# dental-uint-doctors_table_v1_0.net
KiCad netlist of a schematic drawn in Altium Designer
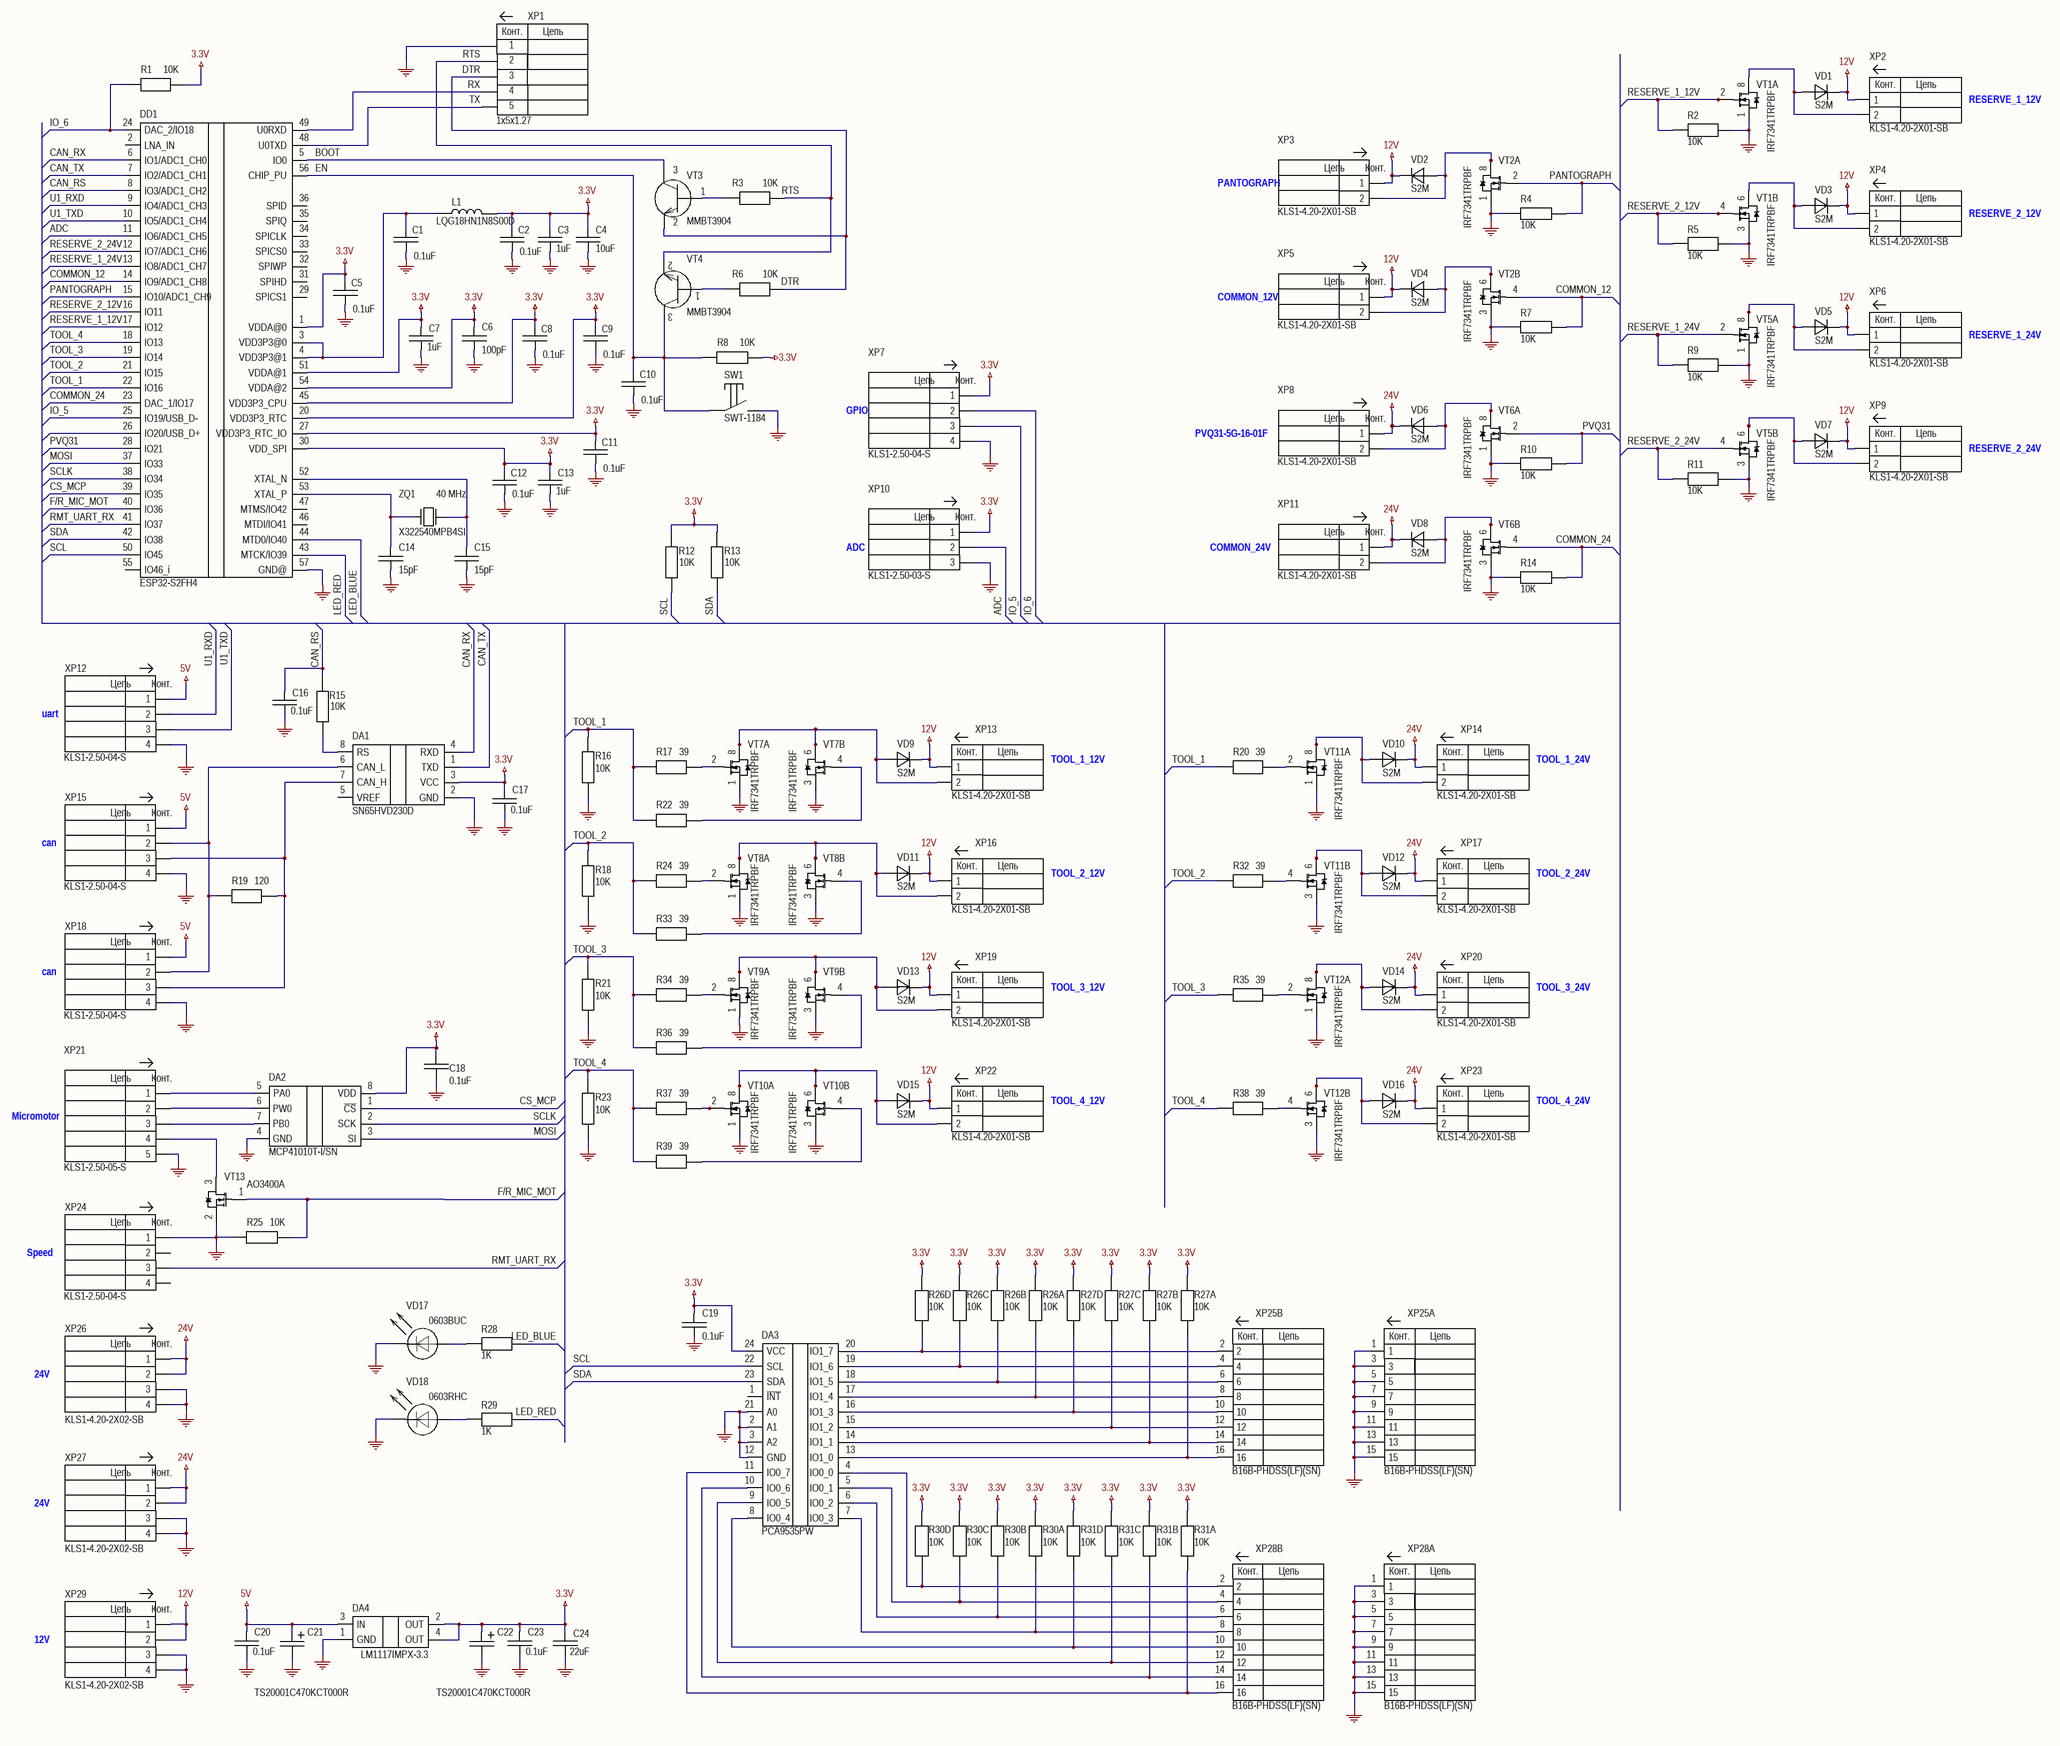
[diagram p0: dental-uint-doctors_table v1_0.SchDoc]

(export (version "E")
  (design (tool "Eeschema 10.0.6"))
  (components
    (comp (ref "C1")
      (value "0.1uF")
      (footprint "CC_0603")
      (description "Cap Ceramic, 0603, 0.1u, 10%, 16V, X7R (Yageo)")
      (fields (field (name "Comment") "CC0603KRX7R5BB104"))
      (libsource (lib "my_discrete_new") (part "C"))
    )
    (comp (ref "C2")
      (value "0.1uF")
      (footprint "CC_0603")
      (description "Cap Ceramic, 0603, 0.1u, 10%, 16V, X7R (Yageo)")
      (fields (field (name "Comment") "CC0603KRX7R5BB104"))
      (libsource (lib "my_discrete_new") (part "C"))
    )
    (comp (ref "C3")
      (value "1uF")
      (footprint "CC_0603")
      (description "Cap Ceramic, 0603, 1u, 10%, 50V, X5R (Sumsung)")
      (fields (field (name "Comment") "CL10A105KB8NNNC"))
      (libsource (lib "my_discrete_new") (part "C"))
    )
    (comp (ref "C4")
      (value "10uF")
      (footprint "CC_0603")
      (description "Cap Ceramic, 0603, 10u, 10%, 16V, X5R (Sumsung)")
      (fields (field (name "Comment") "CL10A106KP8NNNC"))
      (libsource (lib "my_discrete_new") (part "C"))
    )
    (comp (ref "C5")
      (value "0.1uF")
      (footprint "CC_0603")
      (description "Cap Ceramic, 0603, 0.1u, 10%, 16V, X7R (Yageo)")
      (fields (field (name "Comment") "CC0603KRX7R5BB104"))
      (libsource (lib "my_discrete_new") (part "C"))
    )
    (comp (ref "C6")
      (value "100pF")
      (footprint "CC_0603")
      (description "Cap Ceramic, 0603, 100p, 1%, 50V, NP0 (Yageo)")
      (fields (field (name "Comment") "CC0603FRNPO9BN101"))
      (libsource (lib "my_discrete_new") (part "C"))
    )
    (comp (ref "C7")
      (value "1uF")
      (footprint "CC_0603")
      (description "Cap Ceramic, 0603, 1u, 10%, 50V, X5R (Sumsung)")
      (fields (field (name "Comment") "CL10A105KB8NNNC"))
      (libsource (lib "my_discrete_new") (part "C"))
    )
    (comp (ref "C8")
      (value "0.1uF")
      (footprint "CC_0603")
      (description "Cap Ceramic, 0603, 0.1u, 10%, 16V, X7R (Yageo)")
      (fields (field (name "Comment") "CC0603KRX7R5BB104"))
      (libsource (lib "my_discrete_new") (part "C"))
    )
    (comp (ref "C9")
      (value "0.1uF")
      (footprint "CC_0603")
      (description "Cap Ceramic, 0603, 0.1u, 10%, 16V, X7R (Yageo)")
      (fields (field (name "Comment") "CC0603KRX7R5BB104"))
      (libsource (lib "my_discrete_new") (part "C"))
    )
    (comp (ref "C10")
      (value "0.1uF")
      (footprint "CC_0603")
      (description "Cap Ceramic, 0603, 0.1u, 10%, 16V, X7R (Yageo)")
      (fields (field (name "Comment") "CC0603KRX7R5BB104"))
      (libsource (lib "my_discrete_new") (part "C"))
    )
    (comp (ref "C11")
      (value "0.1uF")
      (footprint "CC_0603")
      (description "Cap Ceramic, 0603, 0.1u, 10%, 16V, X7R (Yageo)")
      (fields (field (name "Comment") "CC0603KRX7R5BB104"))
      (libsource (lib "my_discrete_new") (part "C"))
    )
    (comp (ref "C12")
      (value "0.1uF")
      (footprint "CC_0603")
      (description "Cap Ceramic, 0603, 0.1u, 10%, 16V, X7R (Yageo)")
      (fields (field (name "Comment") "CC0603KRX7R5BB104"))
      (libsource (lib "my_discrete_new") (part "C"))
    )
    (comp (ref "C13")
      (value "1uF")
      (footprint "CC_0603")
      (description "Cap Ceramic, 0603, 1u, 10%, 50V, X5R (Sumsung)")
      (fields (field (name "Comment") "CL10A105KB8NNNC"))
      (libsource (lib "my_discrete_new") (part "C"))
    )
    (comp (ref "C14")
      (value "15pF")
      (footprint "CC_0603")
      (description "Cap Ceramic, 0603, 15pF, 50V, NP0 (Yageo)")
      (fields (field (name "Comment") "CC0603GPNPO9BN150"))
      (libsource (lib "my_discrete_new") (part "C"))
    )
    (comp (ref "C15")
      (value "15pF")
      (footprint "CC_0603")
      (description "Cap Ceramic, 0603, 15pF, 50V, NP0 (Yageo)")
      (fields (field (name "Comment") "CC0603GPNPO9BN150"))
      (libsource (lib "my_discrete_new") (part "C"))
    )
    (comp (ref "C16")
      (value "0.1uF")
      (footprint "CC_0603")
      (description "Cap Ceramic, 0603, 0.1u, 10%, 16V, X7R (Yageo)")
      (fields (field (name "Comment") "CC0603KRX7R5BB104"))
      (libsource (lib "my_discrete_new") (part "C"))
    )
    (comp (ref "C17")
      (value "0.1uF")
      (footprint "CC_0603")
      (description "Cap Ceramic, 0603, 0.1u, 10%, 16V, X7R (Yageo)")
      (fields (field (name "Comment") "CC0603KRX7R5BB104"))
      (libsource (lib "my_discrete_new") (part "C"))
    )
    (comp (ref "C18")
      (value "0.1uF")
      (footprint "CC_0603")
      (description "Cap Ceramic, 0603, 0.1u, 10%, 16V, X7R (Yageo)")
      (fields (field (name "Comment") "CC0603KRX7R5BB104"))
      (libsource (lib "my_discrete_new") (part "C"))
    )
    (comp (ref "C19")
      (value "0.1uF")
      (footprint "CC_0603")
      (description "Cap Ceramic, 0603, 0.1u, 10%, 16V, X7R (Yageo)")
      (fields (field (name "Comment") "CC0603KRX7R5BB104"))
      (libsource (lib "my_discrete_new") (part "C"))
    )
    (comp (ref "C20")
      (value "0.1uF")
      (footprint "CC_0603")
      (description "Cap Ceramic, 0603, 0.1u, 10%, 16V, X7R (Yageo)")
      (fields (field (name "Comment") "CC0603KRX7R5BB104"))
      (libsource (lib "my_discrete_new") (part "C"))
    )
    (comp (ref "C21")
      (value "TS20001C470KCT000R")
      (footprint "CC_TANT_C")
      (description "47uF, 16v, C, 10%, @SUNTAN,")
      (libsource (lib "my_discrete_new") (part "C_polar"))
    )
    (comp (ref "C22")
      (value "TS20001C470KCT000R")
      (footprint "CC_TANT_C")
      (description "47uF, 16v, C, 10%, @SUNTAN,")
      (libsource (lib "my_discrete_new") (part "C_polar"))
    )
    (comp (ref "C23")
      (value "0.1uF")
      (footprint "CC_0603")
      (description "Cap Ceramic, 0603, 0.1u, 10%, 16V, X7R (Yageo)")
      (fields (field (name "Comment") "CC0603KRX7R5BB104"))
      (libsource (lib "my_discrete_new") (part "C"))
    )
    (comp (ref "C24")
      (value "22uF")
      (footprint "CC_0805")
      (description "Cap Ceramic, 0805, 22u, 20%, 6.3V, X5R, -55 +85C (Murata)")
      (fields (field (name "Comment") "GRM21BR60J226ME39L"))
      (libsource (lib "my_discrete_new") (part "C"))
    )
    (comp (ref "DA1")
      (value "SN65HVD230D")
      (footprint "SOIC-8")
      (description "3.3-V CAN TRANSCEIVERS, @TI")
      (libsource (lib "my_microschems_new") (part "SN65HVD230D"))
    )
    (comp (ref "DA2")
      (value "MCP41010T-I/SN")
      (footprint "SOIC-8")
      (description "Single/Dual Digital Potentiometer, 10k, @MICROCHIP")
      (libsource (lib "my_microschems_new") (part "MCP41010T-I/SN"))
    )
    (comp (ref "DA3")
      (value "PCA9535PW")
      (footprint "TSSOP-24")
      (description "I2C I/O EXPANDER")
      (libsource (lib "my_microschems_new") (part "PCA9535PW"))
    )
    (comp (ref "DA4")
      (value "LM1117IMPX-3.3")
      (footprint "SOT-223")
      (description "LDO, 3.3v, 0.8A, SOT-223, Texas Instruments")
      (libsource (lib "my_microschems_new") (part "LM1117IMPX-3.3"))
    )
    (comp (ref "DD1")
      (value "ESP32-S2FH4")
      (footprint "QFN40P700X700X90-57T400N")
      (description "SMD WI-FI IC, ESP32-S2FH4, SINGAL-C")
      (fields (field (name "MF") "Espressif Systems") (field (name "MP") "ESP32-S2"))
      (libsource (lib "my_microschems_new") (part "ESP32-S2"))
    )
    (comp (ref "L1")
      (value "LQG18HN1N8S00D")
      (footprint "IC_0603")
      (description "1.1A, 1.8nH,100mΩ, 0603, Inductors (SMD), @MURATA")
      (libsource (lib "my_discrete_new") (part "L"))
    )
    (comp (ref "R1")
      (value "10K")
      (footprint "RC_0603")
      (description "Res, 0603, 10K, 1%, 0.25W (ф. Yageo)")
      (fields (field (name "POWER") "0.25W") (field (name "Comment") "AC0603FR-0710KL"))
      (libsource (lib "my_discrete_new") (part "R"))
    )
    (comp (ref "R2")
      (value "10K")
      (footprint "RC_0603")
      (description "Res, 0603, 10K, 1%, 0.25W (ф. Yageo)")
      (fields (field (name "POWER") "0.25W") (field (name "Comment") "AC0603FR-0710KL"))
      (libsource (lib "my_discrete_new") (part "R"))
    )
    (comp (ref "R3")
      (value "10K")
      (footprint "RC_0603")
      (description "Res, 0603, 10K, 1%, 0.25W (ф. Yageo)")
      (fields (field (name "POWER") "0.25W") (field (name "Comment") "AC0603FR-0710KL"))
      (libsource (lib "my_discrete_new") (part "R"))
    )
    (comp (ref "R4")
      (value "10K")
      (footprint "RC_0603")
      (description "Res, 0603, 10K, 1%, 0.25W (ф. Yageo)")
      (fields (field (name "POWER") "0.25W") (field (name "Comment") "AC0603FR-0710KL"))
      (libsource (lib "my_discrete_new") (part "R"))
    )
    (comp (ref "R5")
      (value "10K")
      (footprint "RC_0603")
      (description "Res, 0603, 10K, 1%, 0.25W (ф. Yageo)")
      (fields (field (name "POWER") "0.25W") (field (name "Comment") "AC0603FR-0710KL"))
      (libsource (lib "my_discrete_new") (part "R"))
    )
    (comp (ref "R6")
      (value "10K")
      (footprint "RC_0603")
      (description "Res, 0603, 10K, 1%, 0.25W (ф. Yageo)")
      (fields (field (name "POWER") "0.25W") (field (name "Comment") "AC0603FR-0710KL"))
      (libsource (lib "my_discrete_new") (part "R"))
    )
    (comp (ref "R7")
      (value "10K")
      (footprint "RC_0603")
      (description "Res, 0603, 10K, 1%, 0.25W (ф. Yageo)")
      (fields (field (name "POWER") "0.25W") (field (name "Comment") "AC0603FR-0710KL"))
      (libsource (lib "my_discrete_new") (part "R"))
    )
    (comp (ref "R8")
      (value "10K")
      (footprint "RC_0603")
      (description "Res, 0603, 10K, 1%, 0.25W (ф. Yageo)")
      (fields (field (name "POWER") "0.25W") (field (name "Comment") "AC0603FR-0710KL"))
      (libsource (lib "my_discrete_new") (part "R"))
    )
    (comp (ref "R9")
      (value "10K")
      (footprint "RC_0603")
      (description "Res, 0603, 10K, 1%, 0.25W (ф. Yageo)")
      (fields (field (name "POWER") "0.25W") (field (name "Comment") "AC0603FR-0710KL"))
      (libsource (lib "my_discrete_new") (part "R"))
    )
    (comp (ref "R10")
      (value "10K")
      (footprint "RC_0603")
      (description "Res, 0603, 10K, 1%, 0.25W (ф. Yageo)")
      (fields (field (name "POWER") "0.25W") (field (name "Comment") "AC0603FR-0710KL"))
      (libsource (lib "my_discrete_new") (part "R"))
    )
    (comp (ref "R11")
      (value "10K")
      (footprint "RC_0603")
      (description "Res, 0603, 10K, 1%, 0.25W (ф. Yageo)")
      (fields (field (name "POWER") "0.25W") (field (name "Comment") "AC0603FR-0710KL"))
      (libsource (lib "my_discrete_new") (part "R"))
    )
    (comp (ref "R12")
      (value "10K")
      (footprint "RC_0603")
      (description "Res, 0603, 10K, 1%, 0.25W (ф. Yageo)")
      (fields (field (name "POWER") "0.25W") (field (name "Comment") "AC0603FR-0710KL"))
      (libsource (lib "my_discrete_new") (part "R"))
    )
    (comp (ref "R13")
      (value "10K")
      (footprint "RC_0603")
      (description "Res, 0603, 10K, 1%, 0.25W (ф. Yageo)")
      (fields (field (name "POWER") "0.25W") (field (name "Comment") "AC0603FR-0710KL"))
      (libsource (lib "my_discrete_new") (part "R"))
    )
    (comp (ref "R14")
      (value "10K")
      (footprint "RC_0603")
      (description "Res, 0603, 10K, 1%, 0.25W (ф. Yageo)")
      (fields (field (name "POWER") "0.25W") (field (name "Comment") "AC0603FR-0710KL"))
      (libsource (lib "my_discrete_new") (part "R"))
    )
    (comp (ref "R15")
      (value "10K")
      (footprint "RC_0603")
      (description "Res, 0603, 10K, 1%, 0.25W (ф. Yageo)")
      (fields (field (name "POWER") "0.25W") (field (name "Comment") "AC0603FR-0710KL"))
      (libsource (lib "my_discrete_new") (part "R"))
    )
    (comp (ref "R16")
      (value "10K")
      (footprint "RC_0603")
      (description "Res, 0603, 10K, 1%, 0.25W (ф. Yageo)")
      (fields (field (name "POWER") "0.25W") (field (name "Comment") "AC0603FR-0710KL"))
      (libsource (lib "my_discrete_new") (part "R"))
    )
    (comp (ref "R17")
      (value "39")
      (footprint "RC_0603")
      (description "Res, 0603, 39, 1%, 0.25W (ф. Yageo)")
      (fields (field (name "POWER") "0.25W") (field (name "Comment") "RC0603FR-0739RL"))
      (libsource (lib "my_discrete_new") (part "R"))
    )
    (comp (ref "R18")
      (value "10K")
      (footprint "RC_0603")
      (description "Res, 0603, 10K, 1%, 0.25W (ф. Yageo)")
      (fields (field (name "POWER") "0.25W") (field (name "Comment") "AC0603FR-0710KL"))
      (libsource (lib "my_discrete_new") (part "R"))
    )
    (comp (ref "R19")
      (value "120")
      (footprint "RC_0603")
      (description "Res, 0603, 120, 1%, 0.25W (ф. Yageo)")
      (fields (field (name "POWER") "0.25W") (field (name "Comment") "RC0603FR-07120RL"))
      (libsource (lib "my_discrete_new") (part "R"))
    )
    (comp (ref "R20")
      (value "39")
      (footprint "RC_0603")
      (description "Res, 0603, 39, 1%, 0.25W (ф. Yageo)")
      (fields (field (name "POWER") "0.25W") (field (name "Comment") "RC0603FR-0739RL"))
      (libsource (lib "my_discrete_new") (part "R"))
    )
    (comp (ref "R21")
      (value "10K")
      (footprint "RC_0603")
      (description "Res, 0603, 10K, 1%, 0.25W (ф. Yageo)")
      (fields (field (name "POWER") "0.25W") (field (name "Comment") "AC0603FR-0710KL"))
      (libsource (lib "my_discrete_new") (part "R"))
    )
    (comp (ref "R22")
      (value "39")
      (footprint "RC_0603")
      (description "Res, 0603, 39, 1%, 0.25W (ф. Yageo)")
      (fields (field (name "POWER") "0.25W") (field (name "Comment") "RC0603FR-0739RL"))
      (libsource (lib "my_discrete_new") (part "R"))
    )
    (comp (ref "R23")
      (value "10K")
      (footprint "RC_0603")
      (description "Res, 0603, 10K, 1%, 0.25W (ф. Yageo)")
      (fields (field (name "POWER") "0.25W") (field (name "Comment") "AC0603FR-0710KL"))
      (libsource (lib "my_discrete_new") (part "R"))
    )
    (comp (ref "R24")
      (value "39")
      (footprint "RC_0603")
      (description "Res, 0603, 39, 1%, 0.25W (ф. Yageo)")
      (fields (field (name "POWER") "0.25W") (field (name "Comment") "RC0603FR-0739RL"))
      (libsource (lib "my_discrete_new") (part "R"))
    )
    (comp (ref "R25")
      (value "10K")
      (footprint "RC_0603")
      (description "Res, 0603, 10K, 1%, 0.25W (ф. Yageo)")
      (fields (field (name "POWER") "0.25W") (field (name "Comment") "AC0603FR-0710KL"))
      (libsource (lib "my_discrete_new") (part "R"))
    )
    (comp (ref "R26")
      (value "10K")
      (footprint "RC_0603x4")
      (description "Res, 0603x4, 10K, 5%, 0.25W (ф. Yageo)")
      (fields (field (name "POWER") "0.25W") (field (name "Comment") "YC164-JR-0710KL"))
      (libsource (lib "my_discrete_new") (part "R_Array"))
    )
    (comp (ref "R27")
      (value "10K")
      (footprint "RC_0603x4")
      (description "Res, 0603x4, 10K, 5%, 0.25W (ф. Yageo)")
      (fields (field (name "POWER") "0.25W") (field (name "Comment") "YC164-JR-0710KL"))
      (libsource (lib "my_discrete_new") (part "R_Array"))
    )
    (comp (ref "R28")
      (value "1K")
      (footprint "RC_0603")
      (description "Res, 0603, 1K 1%, 0.25W (ф. Yageo)")
      (fields (field (name "POWER") "0.25W") (field (name "Comment") "AC0603FR-071KL"))
      (libsource (lib "my_discrete_new") (part "R"))
    )
    (comp (ref "R29")
      (value "1K")
      (footprint "RC_0603")
      (description "Res, 0603, 1K 1%, 0.25W (ф. Yageo)")
      (fields (field (name "POWER") "0.25W") (field (name "Comment") "AC0603FR-071KL"))
      (libsource (lib "my_discrete_new") (part "R"))
    )
    (comp (ref "R30")
      (value "10K")
      (footprint "RC_0603x4")
      (description "Res, 0603x4, 10K, 5%, 0.25W (ф. Yageo)")
      (fields (field (name "POWER") "0.25W") (field (name "Comment") "YC164-JR-0710KL"))
      (libsource (lib "my_discrete_new") (part "R_Array"))
    )
    (comp (ref "R31")
      (value "10K")
      (footprint "RC_0603x4")
      (description "Res, 0603x4, 10K, 5%, 0.25W (ф. Yageo)")
      (fields (field (name "POWER") "0.25W") (field (name "Comment") "YC164-JR-0710KL"))
      (libsource (lib "my_discrete_new") (part "R_Array"))
    )
    (comp (ref "R32")
      (value "39")
      (footprint "RC_0603")
      (description "Res, 0603, 39, 1%, 0.25W (ф. Yageo)")
      (fields (field (name "POWER") "0.25W") (field (name "Comment") "RC0603FR-0739RL"))
      (libsource (lib "my_discrete_new") (part "R"))
    )
    (comp (ref "R33")
      (value "39")
      (footprint "RC_0603")
      (description "Res, 0603, 39, 1%, 0.25W (ф. Yageo)")
      (fields (field (name "POWER") "0.25W") (field (name "Comment") "RC0603FR-0739RL"))
      (libsource (lib "my_discrete_new") (part "R"))
    )
    (comp (ref "R34")
      (value "39")
      (footprint "RC_0603")
      (description "Res, 0603, 39, 1%, 0.25W (ф. Yageo)")
      (fields (field (name "POWER") "0.25W") (field (name "Comment") "RC0603FR-0739RL"))
      (libsource (lib "my_discrete_new") (part "R"))
    )
    (comp (ref "R35")
      (value "39")
      (footprint "RC_0603")
      (description "Res, 0603, 39, 1%, 0.25W (ф. Yageo)")
      (fields (field (name "POWER") "0.25W") (field (name "Comment") "RC0603FR-0739RL"))
      (libsource (lib "my_discrete_new") (part "R"))
    )
    (comp (ref "R36")
      (value "39")
      (footprint "RC_0603")
      (description "Res, 0603, 39, 1%, 0.25W (ф. Yageo)")
      (fields (field (name "POWER") "0.25W") (field (name "Comment") "RC0603FR-0739RL"))
      (libsource (lib "my_discrete_new") (part "R"))
    )
    (comp (ref "R37")
      (value "39")
      (footprint "RC_0603")
      (description "Res, 0603, 39, 1%, 0.25W (ф. Yageo)")
      (fields (field (name "POWER") "0.25W") (field (name "Comment") "RC0603FR-0739RL"))
      (libsource (lib "my_discrete_new") (part "R"))
    )
    (comp (ref "R38")
      (value "39")
      (footprint "RC_0603")
      (description "Res, 0603, 39, 1%, 0.25W (ф. Yageo)")
      (fields (field (name "POWER") "0.25W") (field (name "Comment") "RC0603FR-0739RL"))
      (libsource (lib "my_discrete_new") (part "R"))
    )
    (comp (ref "R39")
      (value "39")
      (footprint "RC_0603")
      (description "Res, 0603, 39, 1%, 0.25W (ф. Yageo)")
      (fields (field (name "POWER") "0.25W") (field (name "Comment") "RC0603FR-0739RL"))
      (libsource (lib "my_discrete_new") (part "R"))
    )
    (comp (ref "SW1")
      (value "SWT-1184")
      (footprint "IT-1184")
      (libsource (lib "my_discrete_new") (part "smd-side-push-button"))
    )
    (comp (ref "VD1")
      (value "S2M")
      (footprint "DO-214AA(SMB)")
      (description "1000В, 2А, 2,5мкс, SMB, @DIODES")
      (libsource (lib "my_discrete_new") (part "D"))
    )
    (comp (ref "VD2")
      (value "S2M")
      (footprint "DO-214AA(SMB)")
      (description "1000В, 2А, 2,5мкс, SMB, @DIODES")
      (libsource (lib "my_discrete_new") (part "D"))
    )
    (comp (ref "VD3")
      (value "S2M")
      (footprint "DO-214AA(SMB)")
      (description "1000В, 2А, 2,5мкс, SMB, @DIODES")
      (libsource (lib "my_discrete_new") (part "D"))
    )
    (comp (ref "VD4")
      (value "S2M")
      (footprint "DO-214AA(SMB)")
      (description "1000В, 2А, 2,5мкс, SMB, @DIODES")
      (libsource (lib "my_discrete_new") (part "D"))
    )
    (comp (ref "VD5")
      (value "S2M")
      (footprint "DO-214AA(SMB)")
      (description "1000В, 2А, 2,5мкс, SMB, @DIODES")
      (libsource (lib "my_discrete_new") (part "D"))
    )
    (comp (ref "VD6")
      (value "S2M")
      (footprint "DO-214AA(SMB)")
      (description "1000В, 2А, 2,5мкс, SMB, @DIODES")
      (libsource (lib "my_discrete_new") (part "D"))
    )
    (comp (ref "VD7")
      (value "S2M")
      (footprint "DO-214AA(SMB)")
      (description "1000В, 2А, 2,5мкс, SMB, @DIODES")
      (libsource (lib "my_discrete_new") (part "D"))
    )
    (comp (ref "VD8")
      (value "S2M")
      (footprint "DO-214AA(SMB)")
      (description "1000В, 2А, 2,5мкс, SMB, @DIODES")
      (libsource (lib "my_discrete_new") (part "D"))
    )
    (comp (ref "VD9")
      (value "S2M")
      (footprint "DO-214AA(SMB)")
      (description "1000В, 2А, 2,5мкс, SMB, @DIODES")
      (libsource (lib "my_discrete_new") (part "D"))
    )
    (comp (ref "VD10")
      (value "S2M")
      (footprint "DO-214AA(SMB)")
      (description "1000В, 2А, 2,5мкс, SMB, @DIODES")
      (libsource (lib "my_discrete_new") (part "D"))
    )
    (comp (ref "VD11")
      (value "S2M")
      (footprint "DO-214AA(SMB)")
      (description "1000В, 2А, 2,5мкс, SMB, @DIODES")
      (libsource (lib "my_discrete_new") (part "D"))
    )
    (comp (ref "VD12")
      (value "S2M")
      (footprint "DO-214AA(SMB)")
      (description "1000В, 2А, 2,5мкс, SMB, @DIODES")
      (libsource (lib "my_discrete_new") (part "D"))
    )
    (comp (ref "VD13")
      (value "S2M")
      (footprint "DO-214AA(SMB)")
      (description "1000В, 2А, 2,5мкс, SMB, @DIODES")
      (libsource (lib "my_discrete_new") (part "D"))
    )
    (comp (ref "VD14")
      (value "S2M")
      (footprint "DO-214AA(SMB)")
      (description "1000В, 2А, 2,5мкс, SMB, @DIODES")
      (libsource (lib "my_discrete_new") (part "D"))
    )
    (comp (ref "VD15")
      (value "S2M")
      (footprint "DO-214AA(SMB)")
      (description "1000В, 2А, 2,5мкс, SMB, @DIODES")
      (libsource (lib "my_discrete_new") (part "D"))
    )
    (comp (ref "VD16")
      (value "S2M")
      (footprint "DO-214AA(SMB)")
      (description "1000В, 2А, 2,5мкс, SMB, @DIODES")
      (libsource (lib "my_discrete_new") (part "D"))
    )
    (comp (ref "VD17")
      (value "0603BUC")
      (footprint "LED_0603")
      (description "Led, 0603, BLUE, 20mA, 125, 140MCD, CPMELEC")
      (libsource (lib "my_discrete_new") (part "LED"))
    )
    (comp (ref "VD18")
      (value "0603RHC")
      (footprint "LED_0603")
      (description "Led, 0603, RED, 20mA, 125, 140MCD, CPMELEC")
      (libsource (lib "my_discrete_new") (part "LED"))
    )
    (comp (ref "VT1")
      (value "IRF7341TRPBF")
      (footprint "SOIC-8")
      (description "Dual N-Channel  MOSFET")
      (libsource (lib "my_microschems_new") (part "IRF7341TRPBF"))
    )
    (comp (ref "VT2")
      (value "IRF7341TRPBF")
      (footprint "SOIC-8")
      (description "Dual N-Channel  MOSFET")
      (libsource (lib "my_microschems_new") (part "IRF7341TRPBF"))
    )
    (comp (ref "VT3")
      (value "MMBT3904")
      (footprint "SOT-23-3")
      (libsource (lib "my_microschems_new") (part "N-P-N-SOT-23"))
    )
    (comp (ref "VT4")
      (value "MMBT3904")
      (footprint "SOT-23-3")
      (libsource (lib "my_microschems_new") (part "N-P-N-SOT-23"))
    )
    (comp (ref "VT5")
      (value "IRF7341TRPBF")
      (footprint "SOIC-8")
      (description "Dual N-Channel  MOSFET")
      (libsource (lib "my_microschems_new") (part "IRF7341TRPBF"))
    )
    (comp (ref "VT6")
      (value "IRF7341TRPBF")
      (footprint "SOIC-8")
      (description "Dual N-Channel  MOSFET")
      (libsource (lib "my_microschems_new") (part "IRF7341TRPBF"))
    )
    (comp (ref "VT7")
      (value "IRF7341TRPBF")
      (footprint "SOIC-8")
      (description "Dual N-Channel  MOSFET")
      (libsource (lib "my_microschems_new") (part "IRF7341TRPBF"))
    )
    (comp (ref "VT8")
      (value "IRF7341TRPBF")
      (footprint "SOIC-8")
      (description "Dual N-Channel  MOSFET")
      (libsource (lib "my_microschems_new") (part "IRF7341TRPBF"))
    )
    (comp (ref "VT9")
      (value "IRF7341TRPBF")
      (footprint "SOIC-8")
      (description "Dual N-Channel  MOSFET")
      (libsource (lib "my_microschems_new") (part "IRF7341TRPBF"))
    )
    (comp (ref "VT10")
      (value "IRF7341TRPBF")
      (footprint "SOIC-8")
      (description "Dual N-Channel  MOSFET")
      (libsource (lib "my_microschems_new") (part "IRF7341TRPBF"))
    )
    (comp (ref "VT11")
      (value "IRF7341TRPBF")
      (footprint "SOIC-8")
      (description "Dual N-Channel  MOSFET")
      (libsource (lib "my_microschems_new") (part "IRF7341TRPBF"))
    )
    (comp (ref "VT12")
      (value "IRF7341TRPBF")
      (footprint "SOIC-8")
      (description "Dual N-Channel  MOSFET")
      (libsource (lib "my_microschems_new") (part "IRF7341TRPBF"))
    )
    (comp (ref "VT13")
      (value "AO3400A")
      (footprint "SOT-23-3")
      (description "N-channel  Power MOSFET, Vds: 30v, Id: 5.7A")
      (libsource (lib "my_microschems_new") (part "AO3400A"))
    )
    (comp (ref "XP1")
      (value "1x5x1.27")
      (footprint "XT_1x5x1.27_offset")
      (libsource (lib "my_connectors_new") (part "XT_1x5x1_27"))
    )
    (comp (ref "XP2")
      (value "KLS1-4.20-2X01-SB")
      (footprint "KLS1-4.20-2X01-SB")
      (description "4.2mm, 2pin, KLS")
      (fields (field (name "NAME") "RESERVE_1_12V"))
      (libsource (lib "my_connectors_new") (part "KLS1-4.20-2X01-x"))
    )
    (comp (ref "XP3")
      (value "KLS1-4.20-2X01-SB")
      (footprint "KLS1-4.20-2X01-SB")
      (description "4.2mm, 2pin, KLS")
      (fields (field (name "NAME") "PANTOGRAPH"))
      (libsource (lib "my_connectors_new") (part "KLS1-4.20-2X01-x"))
    )
    (comp (ref "XP4")
      (value "KLS1-4.20-2X01-SB")
      (footprint "KLS1-4.20-2X01-SB")
      (description "4.2mm, 2pin, KLS")
      (fields (field (name "NAME") "RESERVE_2_12V"))
      (libsource (lib "my_connectors_new") (part "KLS1-4.20-2X01-x"))
    )
    (comp (ref "XP5")
      (value "KLS1-4.20-2X01-SB")
      (footprint "KLS1-4.20-2X01-SB")
      (description "4.2mm, 2pin, KLS")
      (fields (field (name "NAME") "COMMON_12V"))
      (libsource (lib "my_connectors_new") (part "KLS1-4.20-2X01-x"))
    )
    (comp (ref "XP6")
      (value "KLS1-4.20-2X01-SB")
      (footprint "KLS1-4.20-2X01-SB")
      (description "4.2mm, 2pin, KLS")
      (fields (field (name "NAME") "RESERVE_1_24V"))
      (libsource (lib "my_connectors_new") (part "KLS1-4.20-2X01-x"))
    )
    (comp (ref "XP7")
      (value "KLS1-2.50-04-S")
      (footprint "KLS1-2.50-04-S")
      (description "2.5mm, 4pin, KLS")
      (fields (field (name "NAME") "GPIO"))
      (libsource (lib "my_connectors_new") (part "KLS1-2.50-04-x"))
    )
    (comp (ref "XP8")
      (value "KLS1-4.20-2X01-SB")
      (footprint "KLS1-4.20-2X01-SB")
      (description "4.2mm, 2pin, KLS")
      (fields (field (name "NAME") "PVQ31-5G-16-01F"))
      (libsource (lib "my_connectors_new") (part "KLS1-4.20-2X01-x"))
    )
    (comp (ref "XP9")
      (value "KLS1-4.20-2X01-SB")
      (footprint "KLS1-4.20-2X01-SB")
      (description "4.2mm, 2pin, KLS")
      (fields (field (name "NAME") "RESERVE_2_24V"))
      (libsource (lib "my_connectors_new") (part "KLS1-4.20-2X01-x"))
    )
    (comp (ref "XP10")
      (value "KLS1-2.50-03-S")
      (footprint "KLS1-2.50-03-S")
      (description "2.5mm, 3pin, KLS")
      (fields (field (name "NAME") "ADC"))
      (libsource (lib "my_connectors_new") (part "KLS1-2.50-03-x"))
    )
    (comp (ref "XP11")
      (value "KLS1-4.20-2X01-SB")
      (footprint "KLS1-4.20-2X01-SB")
      (description "4.2mm, 2pin, KLS")
      (fields (field (name "NAME") "COMMON_24V"))
      (libsource (lib "my_connectors_new") (part "KLS1-4.20-2X01-x"))
    )
    (comp (ref "XP12")
      (value "KLS1-2.50-04-S")
      (footprint "KLS1-2.50-04-S")
      (description "2.5mm, 4pin, KLS")
      (fields (field (name "NAME") "uart"))
      (libsource (lib "my_connectors_new") (part "KLS1-2.50-04-x"))
    )
    (comp (ref "XP13")
      (value "KLS1-4.20-2X01-SB")
      (footprint "KLS1-4.20-2X01-SB")
      (description "4.2mm, 2pin, KLS")
      (fields (field (name "NAME") "TOOL_1_12V"))
      (libsource (lib "my_connectors_new") (part "KLS1-4.20-2X01-x"))
    )
    (comp (ref "XP14")
      (value "KLS1-4.20-2X01-SB")
      (footprint "KLS1-4.20-2X01-SB")
      (description "4.2mm, 2pin, KLS")
      (fields (field (name "NAME") "TOOL_1_24V"))
      (libsource (lib "my_connectors_new") (part "KLS1-4.20-2X01-x"))
    )
    (comp (ref "XP15")
      (value "KLS1-2.50-04-S")
      (footprint "KLS1-2.50-04-S")
      (description "2.5mm, 4pin, KLS")
      (fields (field (name "NAME") "can"))
      (libsource (lib "my_connectors_new") (part "KLS1-2.50-04-x"))
    )
    (comp (ref "XP16")
      (value "KLS1-4.20-2X01-SB")
      (footprint "KLS1-4.20-2X01-SB")
      (description "4.2mm, 2pin, KLS")
      (fields (field (name "NAME") "TOOL_2_12V"))
      (libsource (lib "my_connectors_new") (part "KLS1-4.20-2X01-x"))
    )
    (comp (ref "XP17")
      (value "KLS1-4.20-2X01-SB")
      (footprint "KLS1-4.20-2X01-SB")
      (description "4.2mm, 2pin, KLS")
      (fields (field (name "NAME") "TOOL_2_24V"))
      (libsource (lib "my_connectors_new") (part "KLS1-4.20-2X01-x"))
    )
    (comp (ref "XP18")
      (value "KLS1-2.50-04-S")
      (footprint "KLS1-2.50-04-S")
      (description "2.5mm, 4pin, KLS")
      (fields (field (name "NAME") "can"))
      (libsource (lib "my_connectors_new") (part "KLS1-2.50-04-x"))
    )
    (comp (ref "XP19")
      (value "KLS1-4.20-2X01-SB")
      (footprint "KLS1-4.20-2X01-SB")
      (description "4.2mm, 2pin, KLS")
      (fields (field (name "NAME") "TOOL_3_12V"))
      (libsource (lib "my_connectors_new") (part "KLS1-4.20-2X01-x"))
    )
    (comp (ref "XP20")
      (value "KLS1-4.20-2X01-SB")
      (footprint "KLS1-4.20-2X01-SB")
      (description "4.2mm, 2pin, KLS")
      (fields (field (name "NAME") "TOOL_3_24V"))
      (libsource (lib "my_connectors_new") (part "KLS1-4.20-2X01-x"))
    )
    (comp (ref "XP21")
      (value "KLS1-2.50-05-S")
      (footprint "KLS1-2.50-05-S")
      (description "2.5mm, 5pin, KLS")
      (fields (field (name "NAME") "Micromotor"))
      (libsource (lib "my_connectors_new") (part "KLS1-2.50-05-x"))
    )
    (comp (ref "XP22")
      (value "KLS1-4.20-2X01-SB")
      (footprint "KLS1-4.20-2X01-SB")
      (description "4.2mm, 2pin, KLS")
      (fields (field (name "NAME") "TOOL_4_12V"))
      (libsource (lib "my_connectors_new") (part "KLS1-4.20-2X01-x"))
    )
    (comp (ref "XP23")
      (value "KLS1-4.20-2X01-SB")
      (footprint "KLS1-4.20-2X01-SB")
      (description "4.2mm, 2pin, KLS")
      (fields (field (name "NAME") "TOOL_4_24V"))
      (libsource (lib "my_connectors_new") (part "KLS1-4.20-2X01-x"))
    )
    (comp (ref "XP24")
      (value "KLS1-2.50-04-S")
      (footprint "KLS1-2.50-04-S")
      (description "2.5mm, 4pin, KLS")
      (fields (field (name "NAME") "Speed"))
      (libsource (lib "my_connectors_new") (part "KLS1-2.50-04-x"))
    )
    (comp (ref "XP25")
      (value "B16B-PHDSS(LF)(SN)")
      (footprint "B16B-PHDSS")
      (libsource (lib "my_connectors_new") (part "B16B-PHDSS(LF)(SN)"))
    )
    (comp (ref "XP26")
      (value "KLS1-4.20-2X02-SB")
      (footprint "KLS1-4.20-2X02-SB")
      (description "4.2mm, 4pin, KLS")
      (fields (field (name "NAME") "24V"))
      (libsource (lib "my_connectors_new") (part "KLS1-4.20-2X02-x"))
    )
    (comp (ref "XP27")
      (value "KLS1-4.20-2X02-SB")
      (footprint "KLS1-4.20-2X02-SB")
      (description "4.2mm, 4pin, KLS")
      (fields (field (name "NAME") "24V"))
      (libsource (lib "my_connectors_new") (part "KLS1-4.20-2X02-x"))
    )
    (comp (ref "XP28")
      (value "B16B-PHDSS(LF)(SN)")
      (footprint "B16B-PHDSS")
      (libsource (lib "my_connectors_new") (part "B16B-PHDSS(LF)(SN)"))
    )
    (comp (ref "XP29")
      (value "KLS1-4.20-2X02-SB")
      (footprint "KLS1-4.20-2X02-SB")
      (description "4.2mm, 4pin, KLS")
      (fields (field (name "NAME") "12V"))
      (libsource (lib "my_connectors_new") (part "KLS1-4.20-2X02-x"))
    )
    (comp (ref "ZQ1")
      (value "X322540MPB4SI")
      (footprint "OSC: 3225")
      (description "40MHz, 15pF, ±10ppm, SMD3225-4P, Crystals ROHS, @YXC")
      (fields (field (name "ALTIUM_VALUE") "40 MHz"))
      (libsource (lib "my_discrete_new") (part "OSC 3225"))
    )
  )
  (nets
    (net (code "1") (name "/ADC") (class "Default")
      (node (ref "DD1") (pin "11") (pinfunction "IO6/ADC1_CH5_11") (pintype "passive"))
      (node (ref "XP10") (pin "2") (pinfunction "2_2") (pintype "passive"))
    )
    (net (code "2") (name "/BOOT") (class "Default")
      (node (ref "DD1") (pin "5") (pinfunction "IO0_5") (pintype "passive"))
      (node (ref "VT3") (pin "3") (pinfunction "C_3") (pintype "passive"))
    )
    (net (code "3") (name "/CAN_RS") (class "Default")
      (node (ref "C16") (pin "2") (pinfunction "2_2") (pintype "passive"))
      (node (ref "DD1") (pin "8") (pinfunction "IO3/ADC1_CH2_8") (pintype "passive"))
      (node (ref "R15") (pin "2") (pinfunction "2_2") (pintype "passive"))
    )
    (net (code "4") (name "/CAN_RX") (class "Default")
      (node (ref "DA1") (pin "4") (pinfunction "RXD_4") (pintype "power_in"))
      (node (ref "DD1") (pin "6") (pinfunction "IO1/ADC1_CH0_6") (pintype "passive"))
    )
    (net (code "5") (name "/CAN_TX") (class "Default")
      (node (ref "DA1") (pin "1") (pinfunction "TXD_1") (pintype "passive"))
      (node (ref "DD1") (pin "7") (pinfunction "IO2/ADC1_CH1_7") (pintype "passive"))
    )
    (net (code "6") (name "/COMMON_12") (class "Default")
      (node (ref "DD1") (pin "14") (pinfunction "IO9/ADC1_CH8_14") (pintype "passive"))
      (node (ref "R7") (pin "1") (pinfunction "1_1") (pintype "passive"))
      (node (ref "VT2") (pin "4") (pinfunction "G2_4") (pintype "passive"))
    )
    (net (code "7") (name "/COMMON_24") (class "Default")
      (node (ref "DD1") (pin "23") (pinfunction "DAC_1/IO17_23") (pintype "passive"))
      (node (ref "R14") (pin "1") (pinfunction "1_1") (pintype "passive"))
      (node (ref "VT6") (pin "4") (pinfunction "G2_4") (pintype "passive"))
    )
    (net (code "8") (name "/CS_MCP") (class "Default")
      (node (ref "DA2") (pin "1") (pinfunction "~{CS}_1") (pintype "passive"))
      (node (ref "DD1") (pin "39") (pinfunction "IO35_39") (pintype "passive"))
    )
    (net (code "9") (name "/DTR") (class "Default")
      (node (ref "R6") (pin "2") (pinfunction "2_2") (pintype "passive"))
      (node (ref "VT3") (pin "2") (pinfunction "E_2") (pintype "passive"))
      (node (ref "XP1") (pin "3") (pinfunction "3_3") (pintype "passive"))
    )
    (net (code "10") (name "/EN") (class "Default")
      (node (ref "C10") (pin "2") (pinfunction "2_2") (pintype "passive"))
      (node (ref "DD1") (pin "56") (pinfunction "CHIP_PU_56") (pintype "passive"))
      (node (ref "R8") (pin "1") (pinfunction "1_1") (pintype "passive"))
      (node (ref "SW1") (pin "1") (pinfunction "1_1") (pintype "passive"))
      (node (ref "VT4") (pin "3") (pinfunction "C_3") (pintype "passive"))
    )
    (net (code "11") (name "/F{slash}R_MIC_MOT") (class "Default")
      (node (ref "DD1") (pin "40") (pinfunction "IO36_40") (pintype "passive"))
      (node (ref "R25") (pin "2") (pinfunction "2_2") (pintype "passive"))
      (node (ref "VT13") (pin "1") (pinfunction "G_1") (pintype "passive"))
    )
    (net (code "12") (name "/IO_5") (class "Default")
      (node (ref "DD1") (pin "25") (pinfunction "IO19/USB_D-_25") (pintype "passive"))
      (node (ref "XP7") (pin "3") (pinfunction "3_3") (pintype "passive"))
    )
    (net (code "13") (name "/IO_6") (class "Default")
      (node (ref "DD1") (pin "24") (pinfunction "DAC_2/IO18_24") (pintype "passive"))
      (node (ref "R1") (pin "1") (pinfunction "1_1") (pintype "passive"))
      (node (ref "XP7") (pin "2") (pinfunction "2_2") (pintype "passive"))
    )
    (net (code "14") (name "/LED_BLUE") (class "Default")
      (node (ref "DD1") (pin "44") (pinfunction "MTD0/IO40_44") (pintype "passive"))
      (node (ref "R28") (pin "1") (pinfunction "1_1") (pintype "passive"))
    )
    (net (code "15") (name "/LED_RED") (class "Default")
      (node (ref "DD1") (pin "43") (pinfunction "MTCK/IO39_43") (pintype "passive"))
      (node (ref "R29") (pin "1") (pinfunction "1_1") (pintype "passive"))
    )
    (net (code "16") (name "/MOSI") (class "Default")
      (node (ref "DA2") (pin "3") (pinfunction "SI_3") (pintype "passive"))
      (node (ref "DD1") (pin "37") (pinfunction "IO33_37") (pintype "passive"))
    )
    (net (code "17") (name "/PANTOGRAPH") (class "Default")
      (node (ref "DD1") (pin "15") (pinfunction "IO10/ADC1_CH9_15") (pintype "passive"))
      (node (ref "R4") (pin "1") (pinfunction "1_1") (pintype "passive"))
      (node (ref "VT2") (pin "2") (pinfunction "G1_2") (pintype "passive"))
    )
    (net (code "18") (name "/PVQ31") (class "Default")
      (node (ref "DD1") (pin "28") (pinfunction "IO21_28") (pintype "passive"))
      (node (ref "R10") (pin "1") (pinfunction "1_1") (pintype "passive"))
      (node (ref "VT6") (pin "2") (pinfunction "G1_2") (pintype "passive"))
    )
    (net (code "19") (name "/RESERVE_1_12V") (class "Default")
      (node (ref "DD1") (pin "17") (pinfunction "IO12_17") (pintype "passive"))
      (node (ref "R2") (pin "1") (pinfunction "1_1") (pintype "passive"))
      (node (ref "VT1") (pin "2") (pinfunction "G1_2") (pintype "passive"))
    )
    (net (code "20") (name "/RESERVE_1_24V") (class "Default")
      (node (ref "DD1") (pin "13") (pinfunction "IO8/ADC1_CH7_13") (pintype "passive"))
      (node (ref "R9") (pin "1") (pinfunction "1_1") (pintype "passive"))
      (node (ref "VT5") (pin "2") (pinfunction "G1_2") (pintype "passive"))
    )
    (net (code "21") (name "/RESERVE_2_12V") (class "Default")
      (node (ref "DD1") (pin "16") (pinfunction "IO11_16") (pintype "passive"))
      (node (ref "R5") (pin "1") (pinfunction "1_1") (pintype "passive"))
      (node (ref "VT1") (pin "4") (pinfunction "G2_4") (pintype "passive"))
    )
    (net (code "22") (name "/RESERVE_2_24V") (class "Default")
      (node (ref "DD1") (pin "12") (pinfunction "IO7/ADC1_CH6_12") (pintype "passive"))
      (node (ref "R11") (pin "1") (pinfunction "1_1") (pintype "passive"))
      (node (ref "VT5") (pin "4") (pinfunction "G2_4") (pintype "passive"))
    )
    (net (code "23") (name "/RMT_UART_RX") (class "Default")
      (node (ref "DD1") (pin "41") (pinfunction "IO37_41") (pintype "passive"))
      (node (ref "XP24") (pin "3") (pinfunction "3_3") (pintype "passive"))
    )
    (net (code "24") (name "/RTS") (class "Default")
      (node (ref "R3") (pin "2") (pinfunction "2_2") (pintype "passive"))
      (node (ref "VT4") (pin "2") (pinfunction "E_2") (pintype "passive"))
      (node (ref "XP1") (pin "2") (pinfunction "2_2") (pintype "passive"))
    )
    (net (code "25") (name "/RX") (class "Default")
      (node (ref "DD1") (pin "49") (pinfunction "U0RXD_49") (pintype "passive"))
      (node (ref "XP1") (pin "4") (pinfunction "4_4") (pintype "passive"))
    )
    (net (code "26") (name "/SCL") (class "Default")
      (node (ref "DA3") (pin "22") (pinfunction "SCL_22") (pintype "passive"))
      (node (ref "DD1") (pin "50") (pinfunction "IO45_50") (pintype "passive"))
      (node (ref "R12") (pin "1") (pinfunction "1_1") (pintype "passive"))
    )
    (net (code "27") (name "/SCLK") (class "Default")
      (node (ref "DA2") (pin "2") (pinfunction "SCK_2") (pintype "passive"))
      (node (ref "DD1") (pin "38") (pinfunction "IO34_38") (pintype "passive"))
    )
    (net (code "28") (name "/SDA") (class "Default")
      (node (ref "DA3") (pin "23") (pinfunction "SDA_23") (pintype "passive"))
      (node (ref "DD1") (pin "42") (pinfunction "IO38_42") (pintype "passive"))
      (node (ref "R13") (pin "1") (pinfunction "1_1") (pintype "passive"))
    )
    (net (code "29") (name "/TOOL_1") (class "Default")
      (node (ref "DD1") (pin "22") (pinfunction "IO16_22") (pintype "passive"))
      (node (ref "R16") (pin "2") (pinfunction "2_2") (pintype "passive"))
      (node (ref "R17") (pin "2") (pinfunction "2_2") (pintype "passive"))
      (node (ref "R20") (pin "2") (pinfunction "2_2") (pintype "passive"))
      (node (ref "R22") (pin "2") (pinfunction "2_2") (pintype "passive"))
    )
    (net (code "30") (name "/TOOL_2") (class "Default")
      (node (ref "DD1") (pin "21") (pinfunction "IO15_21") (pintype "passive"))
      (node (ref "R18") (pin "2") (pinfunction "2_2") (pintype "passive"))
      (node (ref "R24") (pin "2") (pinfunction "2_2") (pintype "passive"))
      (node (ref "R32") (pin "2") (pinfunction "2_2") (pintype "passive"))
      (node (ref "R33") (pin "2") (pinfunction "2_2") (pintype "passive"))
    )
    (net (code "31") (name "/TOOL_3") (class "Default")
      (node (ref "DD1") (pin "19") (pinfunction "IO14_19") (pintype "passive"))
      (node (ref "R21") (pin "2") (pinfunction "2_2") (pintype "passive"))
      (node (ref "R34") (pin "2") (pinfunction "2_2") (pintype "passive"))
      (node (ref "R35") (pin "2") (pinfunction "2_2") (pintype "passive"))
      (node (ref "R36") (pin "2") (pinfunction "2_2") (pintype "passive"))
    )
    (net (code "32") (name "/TOOL_4") (class "Default")
      (node (ref "DD1") (pin "18") (pinfunction "IO13_18") (pintype "passive"))
      (node (ref "R23") (pin "2") (pinfunction "2_2") (pintype "passive"))
      (node (ref "R37") (pin "2") (pinfunction "2_2") (pintype "passive"))
      (node (ref "R38") (pin "2") (pinfunction "2_2") (pintype "passive"))
      (node (ref "R39") (pin "2") (pinfunction "2_2") (pintype "passive"))
    )
    (net (code "33") (name "/TX") (class "Default")
      (node (ref "DD1") (pin "48") (pinfunction "U0TXD_48") (pintype "passive"))
      (node (ref "XP1") (pin "5") (pinfunction "5_5") (pintype "passive"))
    )
    (net (code "34") (name "/U1_RXD") (class "Default")
      (node (ref "DD1") (pin "9") (pinfunction "IO4/ADC1_CH3_9") (pintype "passive"))
      (node (ref "XP12") (pin "2") (pinfunction "2_2") (pintype "passive"))
    )
    (net (code "35") (name "/U1_TXD") (class "Default")
      (node (ref "DD1") (pin "10") (pinfunction "IO5/ADC1_CH4_10") (pintype "passive"))
      (node (ref "XP12") (pin "3") (pinfunction "3_3") (pintype "passive"))
    )
    (net (code "36") (name "3.3V") (class "Default")
      (node (ref "C11") (pin "2") (pinfunction "2_2") (pintype "passive"))
      (node (ref "C12") (pin "2") (pinfunction "2_2") (pintype "passive"))
      (node (ref "C13") (pin "2") (pinfunction "2_2") (pintype "passive"))
      (node (ref "C17") (pin "2") (pinfunction "2_2") (pintype "passive"))
      (node (ref "C18") (pin "2") (pinfunction "2_2") (pintype "passive"))
      (node (ref "C19") (pin "2") (pinfunction "2_2") (pintype "passive"))
      (node (ref "C2") (pin "2") (pinfunction "2_2") (pintype "passive"))
      (node (ref "C22") (pin "1") (pinfunction "1_1") (pintype "passive"))
      (node (ref "C23") (pin "2") (pinfunction "2_2") (pintype "passive"))
      (node (ref "C24") (pin "2") (pinfunction "2_2") (pintype "passive"))
      (node (ref "C3") (pin "2") (pinfunction "2_2") (pintype "passive"))
      (node (ref "C4") (pin "2") (pinfunction "2_2") (pintype "passive"))
      (node (ref "C5") (pin "2") (pinfunction "2_2") (pintype "passive"))
      (node (ref "C6") (pin "2") (pinfunction "2_2") (pintype "passive"))
      (node (ref "C7") (pin "2") (pinfunction "2_2") (pintype "passive"))
      (node (ref "C8") (pin "2") (pinfunction "2_2") (pintype "passive"))
      (node (ref "C9") (pin "2") (pinfunction "2_2") (pintype "passive"))
      (node (ref "DA1") (pin "3") (pinfunction "VCC_3") (pintype "passive"))
      (node (ref "DA2") (pin "8") (pinfunction "VDD_8") (pintype "passive"))
      (node (ref "DA3") (pin "24") (pinfunction "VCC_24") (pintype "power_in"))
      (node (ref "DA4") (pin "2") (pinfunction "OUT_2") (pintype "power_in"))
      (node (ref "DA4") (pin "4") (pinfunction "OUT_4") (pintype "power_in"))
      (node (ref "DD1") (pin "1") (pinfunction "VDDA@0_1") (pintype "passive"))
      (node (ref "DD1") (pin "20") (pinfunction "VDD3P3_RTC_20") (pintype "passive"))
      (node (ref "DD1") (pin "27") (pinfunction "VDD3P3_RTC_IO_27") (pintype "passive"))
      (node (ref "DD1") (pin "30") (pinfunction "VDD_SPI_30") (pintype "passive"))
      (node (ref "DD1") (pin "45") (pinfunction "VDD3P3_CPU_45") (pintype "passive"))
      (node (ref "DD1") (pin "51") (pinfunction "VDDA@1_51") (pintype "passive"))
      (node (ref "DD1") (pin "54") (pinfunction "VDDA@2_54") (pintype "passive"))
      (node (ref "L1") (pin "2") (pinfunction "2_2") (pintype "passive"))
      (node (ref "R1") (pin "2") (pinfunction "2_2") (pintype "passive"))
      (node (ref "R12") (pin "2") (pinfunction "2_2") (pintype "passive"))
      (node (ref "R13") (pin "2") (pinfunction "2_2") (pintype "passive"))
      (node (ref "R26") (pin "5") (pinfunction "5_5") (pintype "passive"))
      (node (ref "R26") (pin "6") (pinfunction "6_6") (pintype "passive"))
      (node (ref "R26") (pin "7") (pinfunction "7_7") (pintype "passive"))
      (node (ref "R26") (pin "8") (pinfunction "8_8") (pintype "passive"))
      (node (ref "R27") (pin "5") (pinfunction "5_5") (pintype "passive"))
      (node (ref "R27") (pin "6") (pinfunction "6_6") (pintype "passive"))
      (node (ref "R27") (pin "7") (pinfunction "7_7") (pintype "passive"))
      (node (ref "R27") (pin "8") (pinfunction "8_8") (pintype "passive"))
      (node (ref "R30") (pin "5") (pinfunction "5_5") (pintype "passive"))
      (node (ref "R30") (pin "6") (pinfunction "6_6") (pintype "passive"))
      (node (ref "R30") (pin "7") (pinfunction "7_7") (pintype "passive"))
      (node (ref "R30") (pin "8") (pinfunction "8_8") (pintype "passive"))
      (node (ref "R31") (pin "5") (pinfunction "5_5") (pintype "passive"))
      (node (ref "R31") (pin "6") (pinfunction "6_6") (pintype "passive"))
      (node (ref "R31") (pin "7") (pinfunction "7_7") (pintype "passive"))
      (node (ref "R31") (pin "8") (pinfunction "8_8") (pintype "passive"))
      (node (ref "R8") (pin "2") (pinfunction "2_2") (pintype "passive"))
      (node (ref "XP10") (pin "1") (pinfunction "1_1") (pintype "passive"))
      (node (ref "XP7") (pin "1") (pinfunction "1_1") (pintype "passive"))
    )
    (net (code "37") (name "5V") (class "Default")
      (node (ref "C20") (pin "2") (pinfunction "2_2") (pintype "passive"))
      (node (ref "C21") (pin "1") (pinfunction "1_1") (pintype "passive"))
      (node (ref "DA4") (pin "3") (pinfunction "IN_3") (pintype "passive"))
      (node (ref "XP12") (pin "1") (pinfunction "1_1") (pintype "passive"))
      (node (ref "XP15") (pin "1") (pinfunction "1_1") (pintype "passive"))
      (node (ref "XP18") (pin "1") (pinfunction "1_1") (pintype "passive"))
    )
    (net (code "38") (name "12V") (class "Default")
      (node (ref "VD1") (pin "2") (pinfunction "C_2") (pintype "passive"))
      (node (ref "VD11") (pin "2") (pinfunction "C_2") (pintype "passive"))
      (node (ref "VD13") (pin "2") (pinfunction "C_2") (pintype "passive"))
      (node (ref "VD15") (pin "2") (pinfunction "C_2") (pintype "passive"))
      (node (ref "VD2") (pin "2") (pinfunction "C_2") (pintype "passive"))
      (node (ref "VD3") (pin "2") (pinfunction "C_2") (pintype "passive"))
      (node (ref "VD4") (pin "2") (pinfunction "C_2") (pintype "passive"))
      (node (ref "VD5") (pin "2") (pinfunction "C_2") (pintype "passive"))
      (node (ref "VD7") (pin "2") (pinfunction "C_2") (pintype "passive"))
      (node (ref "VD9") (pin "2") (pinfunction "C_2") (pintype "passive"))
      (node (ref "XP13") (pin "1") (pinfunction "1_1") (pintype "passive"))
      (node (ref "XP16") (pin "1") (pinfunction "1_1") (pintype "passive"))
      (node (ref "XP19") (pin "1") (pinfunction "1_1") (pintype "passive"))
      (node (ref "XP2") (pin "1") (pinfunction "1_1") (pintype "passive"))
      (node (ref "XP22") (pin "1") (pinfunction "1_1") (pintype "passive"))
      (node (ref "XP29") (pin "1") (pinfunction "1_1") (pintype "passive"))
      (node (ref "XP29") (pin "2") (pinfunction "2_2") (pintype "passive"))
      (node (ref "XP3") (pin "1") (pinfunction "1_1") (pintype "passive"))
      (node (ref "XP4") (pin "1") (pinfunction "1_1") (pintype "passive"))
      (node (ref "XP5") (pin "1") (pinfunction "1_1") (pintype "passive"))
      (node (ref "XP6") (pin "1") (pinfunction "1_1") (pintype "passive"))
      (node (ref "XP9") (pin "1") (pinfunction "1_1") (pintype "passive"))
    )
    (net (code "39") (name "24V") (class "Default")
      (node (ref "VD10") (pin "2") (pinfunction "C_2") (pintype "passive"))
      (node (ref "VD12") (pin "2") (pinfunction "C_2") (pintype "passive"))
      (node (ref "VD14") (pin "2") (pinfunction "C_2") (pintype "passive"))
      (node (ref "VD16") (pin "2") (pinfunction "C_2") (pintype "passive"))
      (node (ref "VD6") (pin "2") (pinfunction "C_2") (pintype "passive"))
      (node (ref "VD8") (pin "2") (pinfunction "C_2") (pintype "passive"))
      (node (ref "XP11") (pin "1") (pinfunction "1_1") (pintype "passive"))
      (node (ref "XP14") (pin "1") (pinfunction "1_1") (pintype "passive"))
      (node (ref "XP17") (pin "1") (pinfunction "1_1") (pintype "passive"))
      (node (ref "XP20") (pin "1") (pinfunction "1_1") (pintype "passive"))
      (node (ref "XP23") (pin "1") (pinfunction "1_1") (pintype "passive"))
      (node (ref "XP26") (pin "1") (pinfunction "1_1") (pintype "passive"))
      (node (ref "XP26") (pin "2") (pinfunction "2_2") (pintype "passive"))
      (node (ref "XP27") (pin "1") (pinfunction "1_1") (pintype "passive"))
      (node (ref "XP27") (pin "2") (pinfunction "2_2") (pintype "passive"))
      (node (ref "XP8") (pin "1") (pinfunction "1_1") (pintype "passive"))
    )
    (net (code "40") (name "GND") (class "Default")
      (node (ref "C1") (pin "1") (pinfunction "1_1") (pintype "passive"))
      (node (ref "C10") (pin "1") (pinfunction "1_1") (pintype "passive"))
      (node (ref "C11") (pin "1") (pinfunction "1_1") (pintype "passive"))
      (node (ref "C12") (pin "1") (pinfunction "1_1") (pintype "passive"))
      (node (ref "C13") (pin "1") (pinfunction "1_1") (pintype "passive"))
      (node (ref "C14") (pin "1") (pinfunction "1_1") (pintype "passive"))
      (node (ref "C15") (pin "1") (pinfunction "1_1") (pintype "passive"))
      (node (ref "C16") (pin "1") (pinfunction "1_1") (pintype "passive"))
      (node (ref "C17") (pin "1") (pinfunction "1_1") (pintype "passive"))
      (node (ref "C18") (pin "1") (pinfunction "1_1") (pintype "passive"))
      (node (ref "C19") (pin "1") (pinfunction "1_1") (pintype "passive"))
      (node (ref "C2") (pin "1") (pinfunction "1_1") (pintype "passive"))
      (node (ref "C20") (pin "1") (pinfunction "1_1") (pintype "passive"))
      (node (ref "C21") (pin "2") (pinfunction "2_2") (pintype "passive"))
      (node (ref "C22") (pin "2") (pinfunction "2_2") (pintype "passive"))
      (node (ref "C23") (pin "1") (pinfunction "1_1") (pintype "passive"))
      (node (ref "C24") (pin "1") (pinfunction "1_1") (pintype "passive"))
      (node (ref "C3") (pin "1") (pinfunction "1_1") (pintype "passive"))
      (node (ref "C4") (pin "1") (pinfunction "1_1") (pintype "passive"))
      (node (ref "C5") (pin "1") (pinfunction "1_1") (pintype "passive"))
      (node (ref "C6") (pin "1") (pinfunction "1_1") (pintype "passive"))
      (node (ref "C7") (pin "1") (pinfunction "1_1") (pintype "passive"))
      (node (ref "C8") (pin "1") (pinfunction "1_1") (pintype "passive"))
      (node (ref "C9") (pin "1") (pinfunction "1_1") (pintype "passive"))
      (node (ref "DA1") (pin "2") (pinfunction "GND_2") (pintype "passive"))
      (node (ref "DA2") (pin "4") (pinfunction "GND_4") (pintype "passive"))
      (node (ref "DA3") (pin "12") (pinfunction "GND_12") (pintype "power_in"))
      (node (ref "DA3") (pin "2") (pinfunction "A1_2") (pintype "passive"))
      (node (ref "DA3") (pin "21") (pinfunction "A0_21") (pintype "passive"))
      (node (ref "DA3") (pin "3") (pinfunction "A2_3") (pintype "passive"))
      (node (ref "DA4") (pin "1") (pinfunction "GND_1") (pintype "passive"))
      (node (ref "DD1") (pin "57") (pinfunction "GND@_57") (pintype "passive"))
      (node (ref "R10") (pin "2") (pinfunction "2_2") (pintype "passive"))
      (node (ref "R11") (pin "2") (pinfunction "2_2") (pintype "passive"))
      (node (ref "R14") (pin "2") (pinfunction "2_2") (pintype "passive"))
      (node (ref "R16") (pin "1") (pinfunction "1_1") (pintype "passive"))
      (node (ref "R18") (pin "1") (pinfunction "1_1") (pintype "passive"))
      (node (ref "R2") (pin "2") (pinfunction "2_2") (pintype "passive"))
      (node (ref "R21") (pin "1") (pinfunction "1_1") (pintype "passive"))
      (node (ref "R23") (pin "1") (pinfunction "1_1") (pintype "passive"))
      (node (ref "R25") (pin "1") (pinfunction "1_1") (pintype "passive"))
      (node (ref "R4") (pin "2") (pinfunction "2_2") (pintype "passive"))
      (node (ref "R5") (pin "2") (pinfunction "2_2") (pintype "passive"))
      (node (ref "R7") (pin "2") (pinfunction "2_2") (pintype "passive"))
      (node (ref "R9") (pin "2") (pinfunction "2_2") (pintype "passive"))
      (node (ref "SW1") (pin "2") (pinfunction "2_2") (pintype "passive"))
      (node (ref "VD17") (pin "2") (pinfunction "C_2") (pintype "passive"))
      (node (ref "VD18") (pin "2") (pinfunction "C_2") (pintype "passive"))
      (node (ref "VT1") (pin "1") (pinfunction "S1_1") (pintype "passive"))
      (node (ref "VT1") (pin "3") (pinfunction "S2_3") (pintype "passive"))
      (node (ref "VT10") (pin "1") (pinfunction "S1_1") (pintype "passive"))
      (node (ref "VT10") (pin "3") (pinfunction "S2_3") (pintype "passive"))
      (node (ref "VT11") (pin "1") (pinfunction "S1_1") (pintype "passive"))
      (node (ref "VT11") (pin "3") (pinfunction "S2_3") (pintype "passive"))
      (node (ref "VT12") (pin "1") (pinfunction "S1_1") (pintype "passive"))
      (node (ref "VT12") (pin "3") (pinfunction "S2_3") (pintype "passive"))
      (node (ref "VT13") (pin "2") (pinfunction "D_2") (pintype "passive"))
      (node (ref "VT2") (pin "1") (pinfunction "S1_1") (pintype "passive"))
      (node (ref "VT2") (pin "3") (pinfunction "S2_3") (pintype "passive"))
      (node (ref "VT5") (pin "1") (pinfunction "S1_1") (pintype "passive"))
      (node (ref "VT5") (pin "3") (pinfunction "S2_3") (pintype "passive"))
      (node (ref "VT6") (pin "1") (pinfunction "S1_1") (pintype "passive"))
      (node (ref "VT6") (pin "3") (pinfunction "S2_3") (pintype "passive"))
      (node (ref "VT7") (pin "1") (pinfunction "S1_1") (pintype "passive"))
      (node (ref "VT7") (pin "3") (pinfunction "S2_3") (pintype "passive"))
      (node (ref "VT8") (pin "1") (pinfunction "S1_1") (pintype "passive"))
      (node (ref "VT8") (pin "3") (pinfunction "S2_3") (pintype "passive"))
      (node (ref "VT9") (pin "1") (pinfunction "S1_1") (pintype "passive"))
      (node (ref "VT9") (pin "3") (pinfunction "S2_3") (pintype "passive"))
      (node (ref "XP1") (pin "1") (pinfunction "1_1") (pintype "passive"))
      (node (ref "XP10") (pin "3") (pinfunction "3_3") (pintype "passive"))
      (node (ref "XP12") (pin "4") (pinfunction "4_4") (pintype "passive"))
      (node (ref "XP15") (pin "4") (pinfunction "4_4") (pintype "passive"))
      (node (ref "XP18") (pin "4") (pinfunction "4_4") (pintype "passive"))
      (node (ref "XP21") (pin "5") (pinfunction "5_5") (pintype "passive"))
      (node (ref "XP24") (pin "1") (pinfunction "1_1") (pintype "passive"))
      (node (ref "XP25") (pin "1") (pinfunction "1_1") (pintype "passive"))
      (node (ref "XP25") (pin "11") (pinfunction "11_11") (pintype "passive"))
      (node (ref "XP25") (pin "13") (pinfunction "13_13") (pintype "passive"))
      (node (ref "XP25") (pin "15") (pinfunction "15_15") (pintype "passive"))
      (node (ref "XP25") (pin "3") (pinfunction "3_3") (pintype "passive"))
      (node (ref "XP25") (pin "5") (pinfunction "5_5") (pintype "passive"))
      (node (ref "XP25") (pin "7") (pinfunction "7_7") (pintype "passive"))
      (node (ref "XP25") (pin "9") (pinfunction "9_9") (pintype "passive"))
      (node (ref "XP26") (pin "3") (pinfunction "3_3") (pintype "passive"))
      (node (ref "XP26") (pin "4") (pinfunction "4_4") (pintype "passive"))
      (node (ref "XP27") (pin "3") (pinfunction "3_3") (pintype "passive"))
      (node (ref "XP27") (pin "4") (pinfunction "4_4") (pintype "passive"))
      (node (ref "XP28") (pin "1") (pinfunction "1_1") (pintype "passive"))
      (node (ref "XP28") (pin "11") (pinfunction "11_11") (pintype "passive"))
      (node (ref "XP28") (pin "13") (pinfunction "13_13") (pintype "passive"))
      (node (ref "XP28") (pin "15") (pinfunction "15_15") (pintype "passive"))
      (node (ref "XP28") (pin "3") (pinfunction "3_3") (pintype "passive"))
      (node (ref "XP28") (pin "5") (pinfunction "5_5") (pintype "passive"))
      (node (ref "XP28") (pin "7") (pinfunction "7_7") (pintype "passive"))
      (node (ref "XP28") (pin "9") (pinfunction "9_9") (pintype "passive"))
      (node (ref "XP29") (pin "3") (pinfunction "3_3") (pintype "passive"))
      (node (ref "XP29") (pin "4") (pinfunction "4_4") (pintype "passive"))
      (node (ref "XP7") (pin "4") (pinfunction "4_4") (pintype "passive"))
    )
    (net (code "41") (name "Net-(DA1-CAN_H)") (class "Default")
      (node (ref "DA1") (pin "7") (pinfunction "CAN_H_7") (pintype "passive"))
      (node (ref "R19") (pin "1") (pinfunction "1_1") (pintype "passive"))
      (node (ref "XP15") (pin "3") (pinfunction "3_3") (pintype "passive"))
      (node (ref "XP18") (pin "3") (pinfunction "3_3") (pintype "passive"))
    )
    (net (code "42") (name "Net-(DA1-CAN_L)") (class "Default")
      (node (ref "DA1") (pin "6") (pinfunction "CAN_L_6") (pintype "passive"))
      (node (ref "R19") (pin "2") (pinfunction "2_2") (pintype "passive"))
      (node (ref "XP15") (pin "2") (pinfunction "2_2") (pintype "passive"))
      (node (ref "XP18") (pin "2") (pinfunction "2_2") (pintype "passive"))
    )
    (net (code "43") (name "Net-(DA1-RS)") (class "Default")
      (node (ref "DA1") (pin "8") (pinfunction "RS_8") (pintype "power_in"))
      (node (ref "R15") (pin "1") (pinfunction "1_1") (pintype "passive"))
    )
    (net (code "44") (name "Net-(DA2-PA0)") (class "Default")
      (node (ref "DA2") (pin "5") (pinfunction "PA0_5") (pintype "passive"))
      (node (ref "XP21") (pin "1") (pinfunction "1_1") (pintype "passive"))
    )
    (net (code "45") (name "Net-(DA2-PB0)") (class "Default")
      (node (ref "DA2") (pin "7") (pinfunction "PB0_7") (pintype "passive"))
      (node (ref "XP21") (pin "3") (pinfunction "3_3") (pintype "passive"))
    )
    (net (code "46") (name "Net-(DA2-PW0)") (class "Default")
      (node (ref "DA2") (pin "6") (pinfunction "PW0_6") (pintype "passive"))
      (node (ref "XP21") (pin "2") (pinfunction "2_2") (pintype "passive"))
    )
    (net (code "47") (name "Net-(DA3-IO0_0)") (class "Default")
      (node (ref "DA3") (pin "4") (pinfunction "IO0_0_4") (pintype "passive"))
      (node (ref "R30") (pin "4") (pinfunction "4_4") (pintype "passive"))
      (node (ref "XP28") (pin "2") (pinfunction "2_2") (pintype "passive"))
    )
    (net (code "48") (name "Net-(DA3-IO0_1)") (class "Default")
      (node (ref "DA3") (pin "5") (pinfunction "IO0_1_5") (pintype "passive"))
      (node (ref "R30") (pin "3") (pinfunction "3_3") (pintype "passive"))
      (node (ref "XP28") (pin "4") (pinfunction "4_4") (pintype "passive"))
    )
    (net (code "49") (name "Net-(DA3-IO0_2)") (class "Default")
      (node (ref "DA3") (pin "6") (pinfunction "IO0_2_6") (pintype "passive"))
      (node (ref "R30") (pin "2") (pinfunction "2_2") (pintype "passive"))
      (node (ref "XP28") (pin "6") (pinfunction "6_6") (pintype "passive"))
    )
    (net (code "50") (name "Net-(DA3-IO0_3)") (class "Default")
      (node (ref "DA3") (pin "7") (pinfunction "IO0_3_7") (pintype "passive"))
      (node (ref "R30") (pin "1") (pinfunction "1_1") (pintype "passive"))
      (node (ref "XP28") (pin "8") (pinfunction "8_8") (pintype "passive"))
    )
    (net (code "51") (name "Net-(DA3-IO0_4)") (class "Default")
      (node (ref "DA3") (pin "8") (pinfunction "IO0_4_8") (pintype "passive"))
      (node (ref "R31") (pin "4") (pinfunction "4_4") (pintype "passive"))
      (node (ref "XP28") (pin "10") (pinfunction "10_10") (pintype "passive"))
    )
    (net (code "52") (name "Net-(DA3-IO0_5)") (class "Default")
      (node (ref "DA3") (pin "9") (pinfunction "IO0_5_9") (pintype "passive"))
      (node (ref "R31") (pin "3") (pinfunction "3_3") (pintype "passive"))
      (node (ref "XP28") (pin "12") (pinfunction "12_12") (pintype "passive"))
    )
    (net (code "53") (name "Net-(DA3-IO0_6)") (class "Default")
      (node (ref "DA3") (pin "10") (pinfunction "IO0_6_10") (pintype "passive"))
      (node (ref "R31") (pin "2") (pinfunction "2_2") (pintype "passive"))
      (node (ref "XP28") (pin "14") (pinfunction "14_14") (pintype "passive"))
    )
    (net (code "54") (name "Net-(DA3-IO0_7)") (class "Default")
      (node (ref "DA3") (pin "11") (pinfunction "IO0_7_11") (pintype "passive"))
      (node (ref "R31") (pin "1") (pinfunction "1_1") (pintype "passive"))
      (node (ref "XP28") (pin "16") (pinfunction "16_16") (pintype "passive"))
    )
    (net (code "55") (name "Net-(DA3-IO1_0)") (class "Default")
      (node (ref "DA3") (pin "13") (pinfunction "IO1_0_13") (pintype "passive"))
      (node (ref "R27") (pin "1") (pinfunction "1_1") (pintype "passive"))
      (node (ref "XP25") (pin "16") (pinfunction "16_16") (pintype "passive"))
    )
    (net (code "56") (name "Net-(DA3-IO1_1)") (class "Default")
      (node (ref "DA3") (pin "14") (pinfunction "IO1_1_14") (pintype "passive"))
      (node (ref "R27") (pin "2") (pinfunction "2_2") (pintype "passive"))
      (node (ref "XP25") (pin "14") (pinfunction "14_14") (pintype "passive"))
    )
    (net (code "57") (name "Net-(DA3-IO1_2)") (class "Default")
      (node (ref "DA3") (pin "15") (pinfunction "IO1_2_15") (pintype "passive"))
      (node (ref "R27") (pin "3") (pinfunction "3_3") (pintype "passive"))
      (node (ref "XP25") (pin "12") (pinfunction "12_12") (pintype "passive"))
    )
    (net (code "58") (name "Net-(DA3-IO1_3)") (class "Default")
      (node (ref "DA3") (pin "16") (pinfunction "IO1_3_16") (pintype "passive"))
      (node (ref "R27") (pin "4") (pinfunction "4_4") (pintype "passive"))
      (node (ref "XP25") (pin "10") (pinfunction "10_10") (pintype "passive"))
    )
    (net (code "59") (name "Net-(DA3-IO1_4)") (class "Default")
      (node (ref "DA3") (pin "17") (pinfunction "IO1_4_17") (pintype "passive"))
      (node (ref "R26") (pin "1") (pinfunction "1_1") (pintype "passive"))
      (node (ref "XP25") (pin "8") (pinfunction "8_8") (pintype "passive"))
    )
    (net (code "60") (name "Net-(DA3-IO1_5)") (class "Default")
      (node (ref "DA3") (pin "18") (pinfunction "IO1_5_18") (pintype "passive"))
      (node (ref "R26") (pin "2") (pinfunction "2_2") (pintype "passive"))
      (node (ref "XP25") (pin "6") (pinfunction "6_6") (pintype "passive"))
    )
    (net (code "61") (name "Net-(DA3-IO1_6)") (class "Default")
      (node (ref "DA3") (pin "19") (pinfunction "IO1_6_19") (pintype "passive"))
      (node (ref "R26") (pin "3") (pinfunction "3_3") (pintype "passive"))
      (node (ref "XP25") (pin "4") (pinfunction "4_4") (pintype "passive"))
    )
    (net (code "62") (name "Net-(DA3-IO1_7)") (class "Default")
      (node (ref "DA3") (pin "20") (pinfunction "IO1_7_20") (pintype "passive"))
      (node (ref "R26") (pin "4") (pinfunction "4_4") (pintype "passive"))
      (node (ref "XP25") (pin "2") (pinfunction "2_2") (pintype "passive"))
    )
    (net (code "63") (name "Net-(DD1-VDD3P3@0)") (class "Default")
      (node (ref "C1") (pin "2") (pinfunction "2_2") (pintype "passive"))
      (node (ref "DD1") (pin "3") (pinfunction "VDD3P3@0_3") (pintype "passive"))
      (node (ref "DD1") (pin "4") (pinfunction "VDD3P3@1_4") (pintype "passive"))
      (node (ref "L1") (pin "1") (pinfunction "1_1") (pintype "passive"))
    )
    (net (code "64") (name "Net-(DD1-XTAL_N)") (class "Default")
      (node (ref "C15") (pin "2") (pinfunction "2_2") (pintype "passive"))
      (node (ref "DD1") (pin "52") (pinfunction "XTAL_N_52") (pintype "passive"))
      (node (ref "ZQ1") (pin "3") (pinfunction "3_3") (pintype "passive"))
    )
    (net (code "65") (name "Net-(DD1-XTAL_P)") (class "Default")
      (node (ref "C14") (pin "2") (pinfunction "2_2") (pintype "passive"))
      (node (ref "DD1") (pin "53") (pinfunction "XTAL_P_53") (pintype "passive"))
      (node (ref "ZQ1") (pin "1") (pinfunction "1_1") (pintype "passive"))
    )
    (net (code "66") (name "Net-(VD1-A)") (class "Default")
      (node (ref "VD1") (pin "1") (pinfunction "A_1") (pintype "passive"))
      (node (ref "VT1") (pin "7") (pinfunction "D1_7") (pintype "passive"))
      (node (ref "VT1") (pin "8") (pinfunction "D1_8") (pintype "passive"))
      (node (ref "XP2") (pin "2") (pinfunction "2_2") (pintype "passive"))
    )
    (net (code "67") (name "Net-(VD2-A)") (class "Default")
      (node (ref "VD2") (pin "1") (pinfunction "A_1") (pintype "passive"))
      (node (ref "VT2") (pin "7") (pinfunction "D1_7") (pintype "passive"))
      (node (ref "VT2") (pin "8") (pinfunction "D1_8") (pintype "passive"))
      (node (ref "XP3") (pin "2") (pinfunction "2_2") (pintype "passive"))
    )
    (net (code "68") (name "Net-(VD3-A)") (class "Default")
      (node (ref "VD3") (pin "1") (pinfunction "A_1") (pintype "passive"))
      (node (ref "VT1") (pin "5") (pinfunction "D1_5") (pintype "passive"))
      (node (ref "VT1") (pin "6") (pinfunction "D1_6") (pintype "passive"))
      (node (ref "XP4") (pin "2") (pinfunction "2_2") (pintype "passive"))
    )
    (net (code "69") (name "Net-(VD4-A)") (class "Default")
      (node (ref "VD4") (pin "1") (pinfunction "A_1") (pintype "passive"))
      (node (ref "VT2") (pin "5") (pinfunction "D1_5") (pintype "passive"))
      (node (ref "VT2") (pin "6") (pinfunction "D1_6") (pintype "passive"))
      (node (ref "XP5") (pin "2") (pinfunction "2_2") (pintype "passive"))
    )
    (net (code "70") (name "Net-(VD5-A)") (class "Default")
      (node (ref "VD5") (pin "1") (pinfunction "A_1") (pintype "passive"))
      (node (ref "VT5") (pin "7") (pinfunction "D1_7") (pintype "passive"))
      (node (ref "VT5") (pin "8") (pinfunction "D1_8") (pintype "passive"))
      (node (ref "XP6") (pin "2") (pinfunction "2_2") (pintype "passive"))
    )
    (net (code "71") (name "Net-(VD6-A)") (class "Default")
      (node (ref "VD6") (pin "1") (pinfunction "A_1") (pintype "passive"))
      (node (ref "VT6") (pin "7") (pinfunction "D1_7") (pintype "passive"))
      (node (ref "VT6") (pin "8") (pinfunction "D1_8") (pintype "passive"))
      (node (ref "XP8") (pin "2") (pinfunction "2_2") (pintype "passive"))
    )
    (net (code "72") (name "Net-(VD7-A)") (class "Default")
      (node (ref "VD7") (pin "1") (pinfunction "A_1") (pintype "passive"))
      (node (ref "VT5") (pin "5") (pinfunction "D1_5") (pintype "passive"))
      (node (ref "VT5") (pin "6") (pinfunction "D1_6") (pintype "passive"))
      (node (ref "XP9") (pin "2") (pinfunction "2_2") (pintype "passive"))
    )
    (net (code "73") (name "Net-(VD8-A)") (class "Default")
      (node (ref "VD8") (pin "1") (pinfunction "A_1") (pintype "passive"))
      (node (ref "VT6") (pin "5") (pinfunction "D1_5") (pintype "passive"))
      (node (ref "VT6") (pin "6") (pinfunction "D1_6") (pintype "passive"))
      (node (ref "XP11") (pin "2") (pinfunction "2_2") (pintype "passive"))
    )
    (net (code "74") (name "Net-(VD9-A)") (class "Default")
      (node (ref "VD9") (pin "1") (pinfunction "A_1") (pintype "passive"))
      (node (ref "VT7") (pin "5") (pinfunction "D1_5") (pintype "passive"))
      (node (ref "VT7") (pin "6") (pinfunction "D1_6") (pintype "passive"))
      (node (ref "VT7") (pin "7") (pinfunction "D1_7") (pintype "passive"))
      (node (ref "VT7") (pin "8") (pinfunction "D1_8") (pintype "passive"))
      (node (ref "XP13") (pin "2") (pinfunction "2_2") (pintype "passive"))
    )
    (net (code "75") (name "Net-(VD10-A)") (class "Default")
      (node (ref "VD10") (pin "1") (pinfunction "A_1") (pintype "passive"))
      (node (ref "VT11") (pin "7") (pinfunction "D1_7") (pintype "passive"))
      (node (ref "VT11") (pin "8") (pinfunction "D1_8") (pintype "passive"))
      (node (ref "XP14") (pin "2") (pinfunction "2_2") (pintype "passive"))
    )
    (net (code "76") (name "Net-(VD11-A)") (class "Default")
      (node (ref "VD11") (pin "1") (pinfunction "A_1") (pintype "passive"))
      (node (ref "VT8") (pin "5") (pinfunction "D1_5") (pintype "passive"))
      (node (ref "VT8") (pin "6") (pinfunction "D1_6") (pintype "passive"))
      (node (ref "VT8") (pin "7") (pinfunction "D1_7") (pintype "passive"))
      (node (ref "VT8") (pin "8") (pinfunction "D1_8") (pintype "passive"))
      (node (ref "XP16") (pin "2") (pinfunction "2_2") (pintype "passive"))
    )
    (net (code "77") (name "Net-(VD12-A)") (class "Default")
      (node (ref "VD12") (pin "1") (pinfunction "A_1") (pintype "passive"))
      (node (ref "VT11") (pin "5") (pinfunction "D1_5") (pintype "passive"))
      (node (ref "VT11") (pin "6") (pinfunction "D1_6") (pintype "passive"))
      (node (ref "XP17") (pin "2") (pinfunction "2_2") (pintype "passive"))
    )
    (net (code "78") (name "Net-(VD13-A)") (class "Default")
      (node (ref "VD13") (pin "1") (pinfunction "A_1") (pintype "passive"))
      (node (ref "VT9") (pin "5") (pinfunction "D1_5") (pintype "passive"))
      (node (ref "VT9") (pin "6") (pinfunction "D1_6") (pintype "passive"))
      (node (ref "VT9") (pin "7") (pinfunction "D1_7") (pintype "passive"))
      (node (ref "VT9") (pin "8") (pinfunction "D1_8") (pintype "passive"))
      (node (ref "XP19") (pin "2") (pinfunction "2_2") (pintype "passive"))
    )
    (net (code "79") (name "Net-(VD14-A)") (class "Default")
      (node (ref "VD14") (pin "1") (pinfunction "A_1") (pintype "passive"))
      (node (ref "VT12") (pin "7") (pinfunction "D1_7") (pintype "passive"))
      (node (ref "VT12") (pin "8") (pinfunction "D1_8") (pintype "passive"))
      (node (ref "XP20") (pin "2") (pinfunction "2_2") (pintype "passive"))
    )
    (net (code "80") (name "Net-(VD15-A)") (class "Default")
      (node (ref "VD15") (pin "1") (pinfunction "A_1") (pintype "passive"))
      (node (ref "VT10") (pin "5") (pinfunction "D1_5") (pintype "passive"))
      (node (ref "VT10") (pin "6") (pinfunction "D1_6") (pintype "passive"))
      (node (ref "VT10") (pin "7") (pinfunction "D1_7") (pintype "passive"))
      (node (ref "VT10") (pin "8") (pinfunction "D1_8") (pintype "passive"))
      (node (ref "XP22") (pin "2") (pinfunction "2_2") (pintype "passive"))
    )
    (net (code "81") (name "Net-(VD16-A)") (class "Default")
      (node (ref "VD16") (pin "1") (pinfunction "A_1") (pintype "passive"))
      (node (ref "VT12") (pin "5") (pinfunction "D1_5") (pintype "passive"))
      (node (ref "VT12") (pin "6") (pinfunction "D1_6") (pintype "passive"))
      (node (ref "XP23") (pin "2") (pinfunction "2_2") (pintype "passive"))
    )
    (net (code "82") (name "Net-(VD17-A)") (class "Default")
      (node (ref "R28") (pin "2") (pinfunction "2_2") (pintype "passive"))
      (node (ref "VD17") (pin "1") (pinfunction "A_1") (pintype "passive"))
    )
    (net (code "83") (name "Net-(VD18-A)") (class "Default")
      (node (ref "R29") (pin "2") (pinfunction "2_2") (pintype "passive"))
      (node (ref "VD18") (pin "1") (pinfunction "A_1") (pintype "passive"))
    )
    (net (code "84") (name "Net-(VT3-B)") (class "Default")
      (node (ref "R3") (pin "1") (pinfunction "1_1") (pintype "passive"))
      (node (ref "VT3") (pin "1") (pinfunction "B_1") (pintype "passive"))
    )
    (net (code "85") (name "Net-(VT4-B)") (class "Default")
      (node (ref "R6") (pin "1") (pinfunction "1_1") (pintype "passive"))
      (node (ref "VT4") (pin "1") (pinfunction "B_1") (pintype "passive"))
    )
    (net (code "86") (name "Net-(VT7A-G1)") (class "Default")
      (node (ref "R17") (pin "1") (pinfunction "1_1") (pintype "passive"))
      (node (ref "VT7") (pin "2") (pinfunction "G1_2") (pintype "passive"))
    )
    (net (code "87") (name "Net-(VT7B-G2)") (class "Default")
      (node (ref "R22") (pin "1") (pinfunction "1_1") (pintype "passive"))
      (node (ref "VT7") (pin "4") (pinfunction "G2_4") (pintype "passive"))
    )
    (net (code "88") (name "Net-(VT8A-G1)") (class "Default")
      (node (ref "R24") (pin "1") (pinfunction "1_1") (pintype "passive"))
      (node (ref "VT8") (pin "2") (pinfunction "G1_2") (pintype "passive"))
    )
    (net (code "89") (name "Net-(VT8B-G2)") (class "Default")
      (node (ref "R33") (pin "1") (pinfunction "1_1") (pintype "passive"))
      (node (ref "VT8") (pin "4") (pinfunction "G2_4") (pintype "passive"))
    )
    (net (code "90") (name "Net-(VT9A-G1)") (class "Default")
      (node (ref "R34") (pin "1") (pinfunction "1_1") (pintype "passive"))
      (node (ref "VT9") (pin "2") (pinfunction "G1_2") (pintype "passive"))
    )
    (net (code "91") (name "Net-(VT9B-G2)") (class "Default")
      (node (ref "R36") (pin "1") (pinfunction "1_1") (pintype "passive"))
      (node (ref "VT9") (pin "4") (pinfunction "G2_4") (pintype "passive"))
    )
    (net (code "92") (name "Net-(VT10A-G1)") (class "Default")
      (node (ref "R37") (pin "1") (pinfunction "1_1") (pintype "passive"))
      (node (ref "VT10") (pin "2") (pinfunction "G1_2") (pintype "passive"))
    )
    (net (code "93") (name "Net-(VT10B-G2)") (class "Default")
      (node (ref "R39") (pin "1") (pinfunction "1_1") (pintype "passive"))
      (node (ref "VT10") (pin "4") (pinfunction "G2_4") (pintype "passive"))
    )
    (net (code "94") (name "Net-(VT11A-G1)") (class "Default")
      (node (ref "R20") (pin "1") (pinfunction "1_1") (pintype "passive"))
      (node (ref "VT11") (pin "2") (pinfunction "G1_2") (pintype "passive"))
    )
    (net (code "95") (name "Net-(VT11B-G2)") (class "Default")
      (node (ref "R32") (pin "1") (pinfunction "1_1") (pintype "passive"))
      (node (ref "VT11") (pin "4") (pinfunction "G2_4") (pintype "passive"))
    )
    (net (code "96") (name "Net-(VT12A-G1)") (class "Default")
      (node (ref "R35") (pin "1") (pinfunction "1_1") (pintype "passive"))
      (node (ref "VT12") (pin "2") (pinfunction "G1_2") (pintype "passive"))
    )
    (net (code "97") (name "Net-(VT12B-G2)") (class "Default")
      (node (ref "R38") (pin "1") (pinfunction "1_1") (pintype "passive"))
      (node (ref "VT12") (pin "4") (pinfunction "G2_4") (pintype "passive"))
    )
    (net (code "98") (name "Net-(VT13-S)") (class "Default")
      (node (ref "VT13") (pin "3") (pinfunction "S_3") (pintype "passive"))
      (node (ref "XP21") (pin "4") (pinfunction "4_4") (pintype "passive"))
    )
    (net (code "99") (name "unconnected-(DA1-VREF-Pad5)") (class "Default")
      (node (ref "DA1") (pin "5") (pinfunction "VREF_5") (pintype "passive"))
    )
    (net (code "100") (name "unconnected-(DA3-~{INT}-Pad1)") (class "Default")
      (node (ref "DA3") (pin "1") (pinfunction "~{INT}_1") (pintype "passive"))
    )
    (net (code "101") (name "unconnected-(DD1-IO20{slash}USB_D+-Pad26)") (class "Default")
      (node (ref "DD1") (pin "26") (pinfunction "IO20/USB_D+_26") (pintype "passive"))
    )
    (net (code "102") (name "unconnected-(DD1-IO46_i-Pad55)") (class "Default")
      (node (ref "DD1") (pin "55") (pinfunction "IO46_i_55") (pintype "passive"))
    )
    (net (code "103") (name "unconnected-(DD1-LNA_IN-Pad2)") (class "Default")
      (node (ref "DD1") (pin "2") (pinfunction "LNA_IN_2") (pintype "passive"))
    )
    (net (code "104") (name "unconnected-(DD1-MTDI{slash}IO41-Pad46)") (class "Default")
      (node (ref "DD1") (pin "46") (pinfunction "MTDI/IO41_46") (pintype "passive"))
    )
    (net (code "105") (name "unconnected-(DD1-MTMS{slash}IO42-Pad47)") (class "Default")
      (node (ref "DD1") (pin "47") (pinfunction "MTMS/IO42_47") (pintype "passive"))
    )
    (net (code "106") (name "unconnected-(DD1-SPICLK-Pad34)") (class "Default")
      (node (ref "DD1") (pin "34") (pinfunction "SPICLK_34") (pintype "passive"))
    )
    (net (code "107") (name "unconnected-(DD1-SPICS0-Pad33)") (class "Default")
      (node (ref "DD1") (pin "33") (pinfunction "SPICS0_33") (pintype "passive"))
    )
    (net (code "108") (name "unconnected-(DD1-SPICS1-Pad29)") (class "Default")
      (node (ref "DD1") (pin "29") (pinfunction "SPICS1_29") (pintype "passive"))
    )
    (net (code "109") (name "unconnected-(DD1-SPID-Pad36)") (class "Default")
      (node (ref "DD1") (pin "36") (pinfunction "SPID_36") (pintype "passive"))
    )
    (net (code "110") (name "unconnected-(DD1-SPIHD-Pad31)") (class "Default")
      (node (ref "DD1") (pin "31") (pinfunction "SPIHD_31") (pintype "passive"))
    )
    (net (code "111") (name "unconnected-(DD1-SPIQ-Pad35)") (class "Default")
      (node (ref "DD1") (pin "35") (pinfunction "SPIQ_35") (pintype "passive"))
    )
    (net (code "112") (name "unconnected-(DD1-SPIWP-Pad32)") (class "Default")
      (node (ref "DD1") (pin "32") (pinfunction "SPIWP_32") (pintype "passive"))
    )
    (net (code "113") (name "unconnected-(XP24-Pad2)") (class "Default")
      (node (ref "XP24") (pin "2") (pinfunction "2_2") (pintype "passive"))
    )
    (net (code "114") (name "unconnected-(XP24-Pad4)") (class "Default")
      (node (ref "XP24") (pin "4") (pinfunction "4_4") (pintype "passive"))
    )
    (net (code "115") (name "unconnected-(ZQ1-Pad2)") (class "Default")
      (node (ref "ZQ1") (pin "2") (pinfunction "2_2") (pintype "passive"))
    )
    (net (code "116") (name "unconnected-(ZQ1-Pad4)") (class "Default")
      (node (ref "ZQ1") (pin "4") (pinfunction "4_4") (pintype "passive"))
    )
  )
)
